# blinds_v60.net
KiCad netlist of a schematic drawn in EAGLE
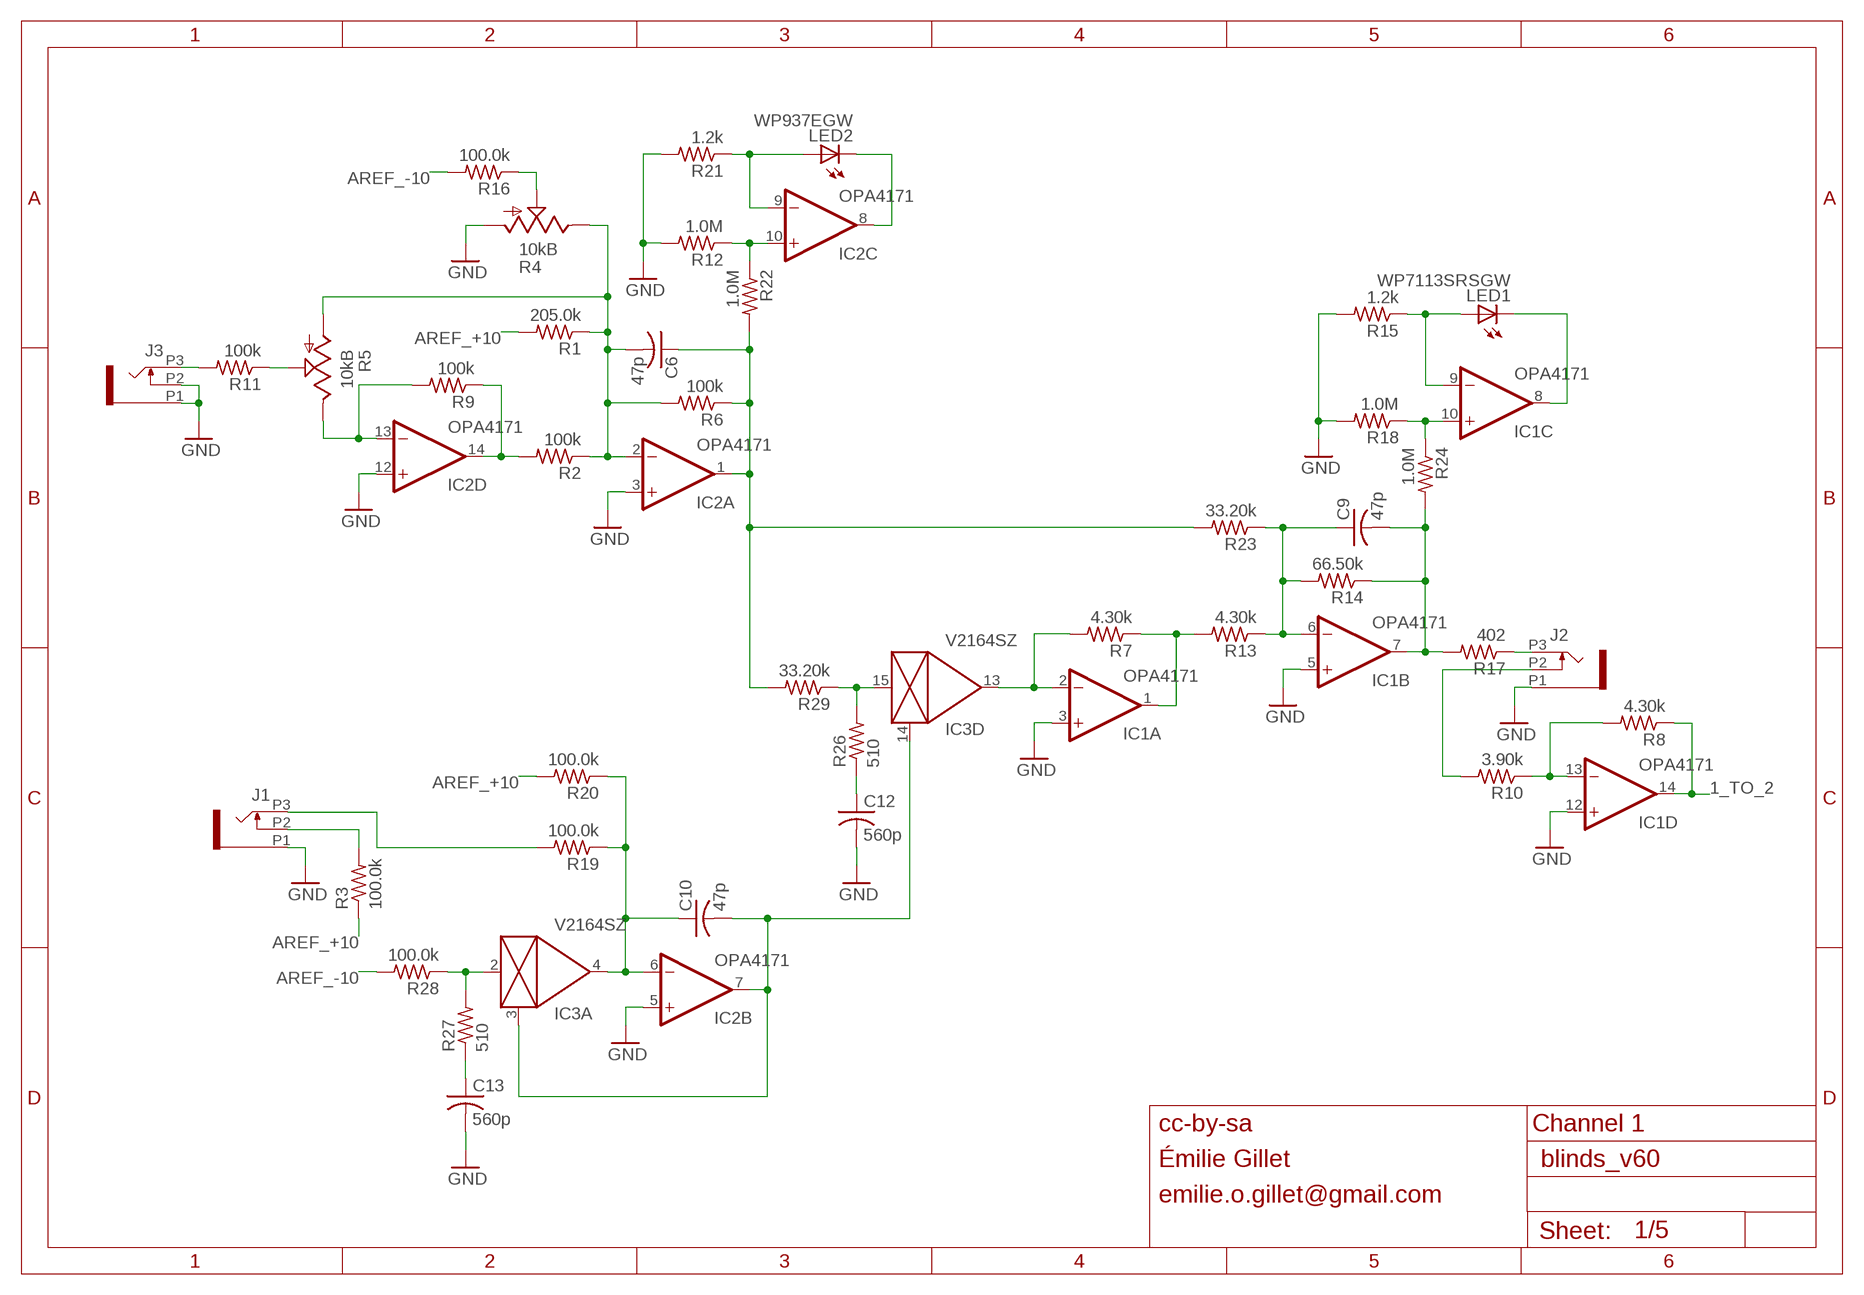
[diagram p0: schematic, sheet 1]
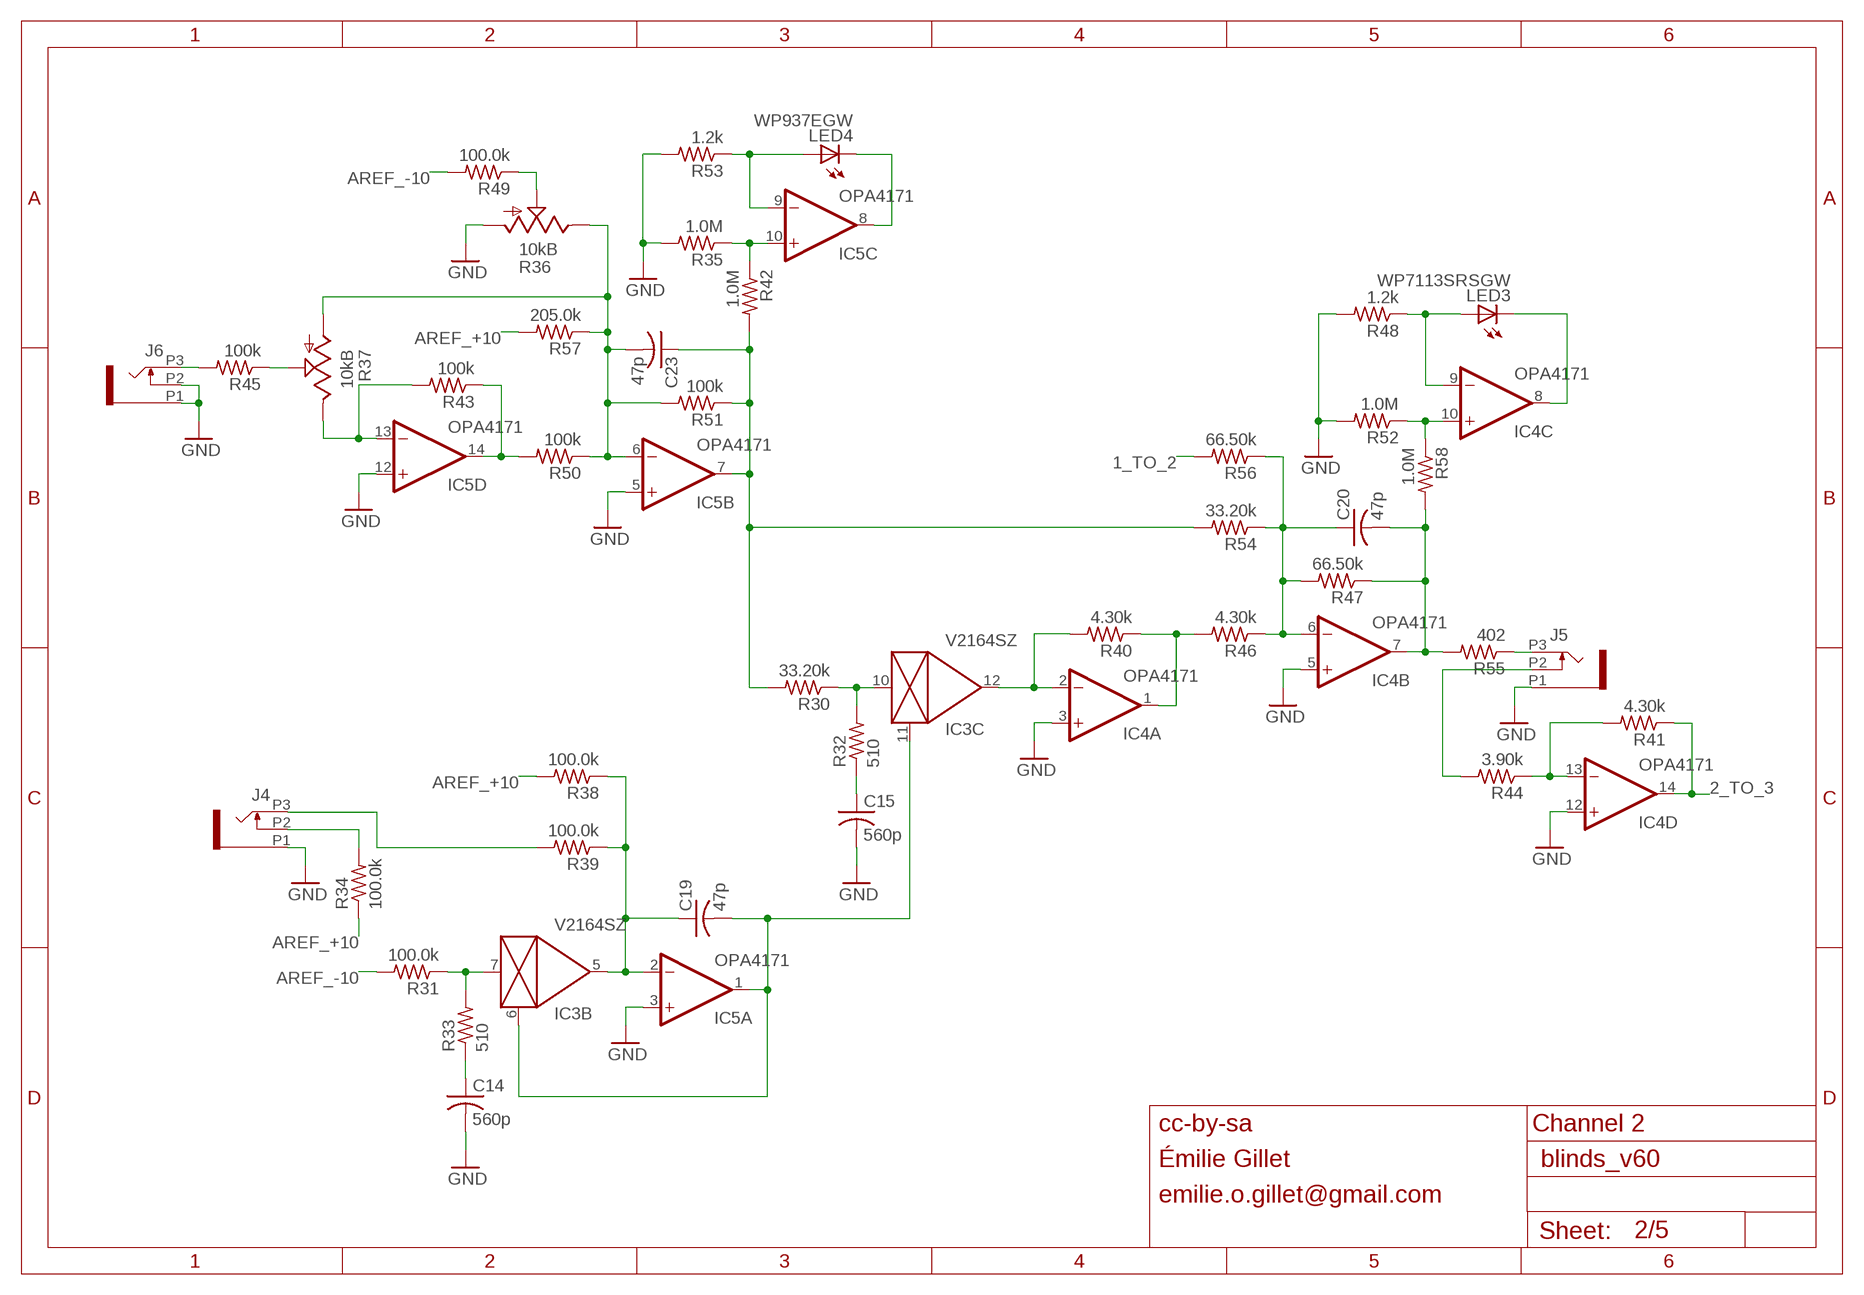
[diagram p1: schematic, sheet 2]
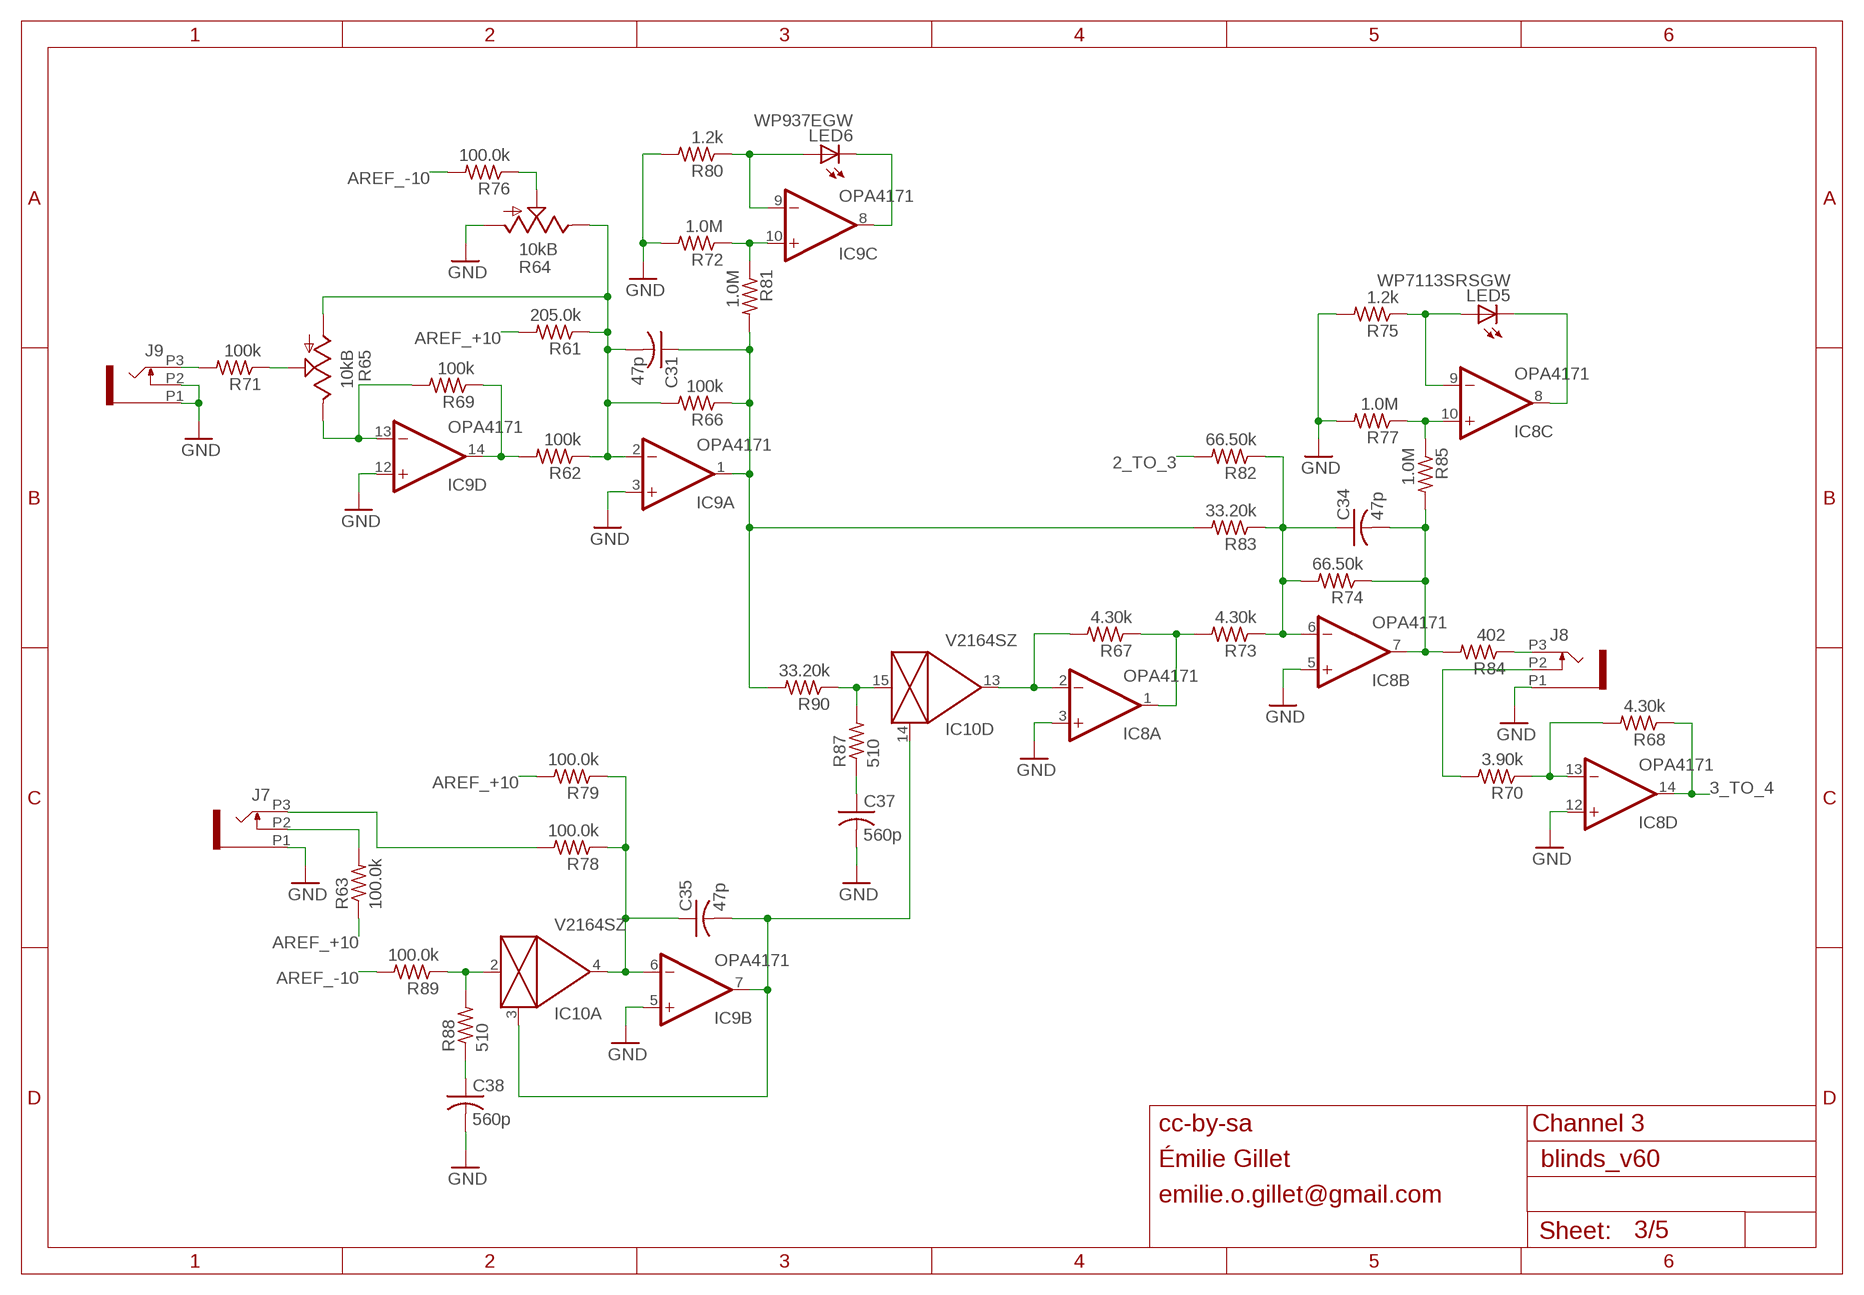
[diagram p2: schematic, sheet 3]
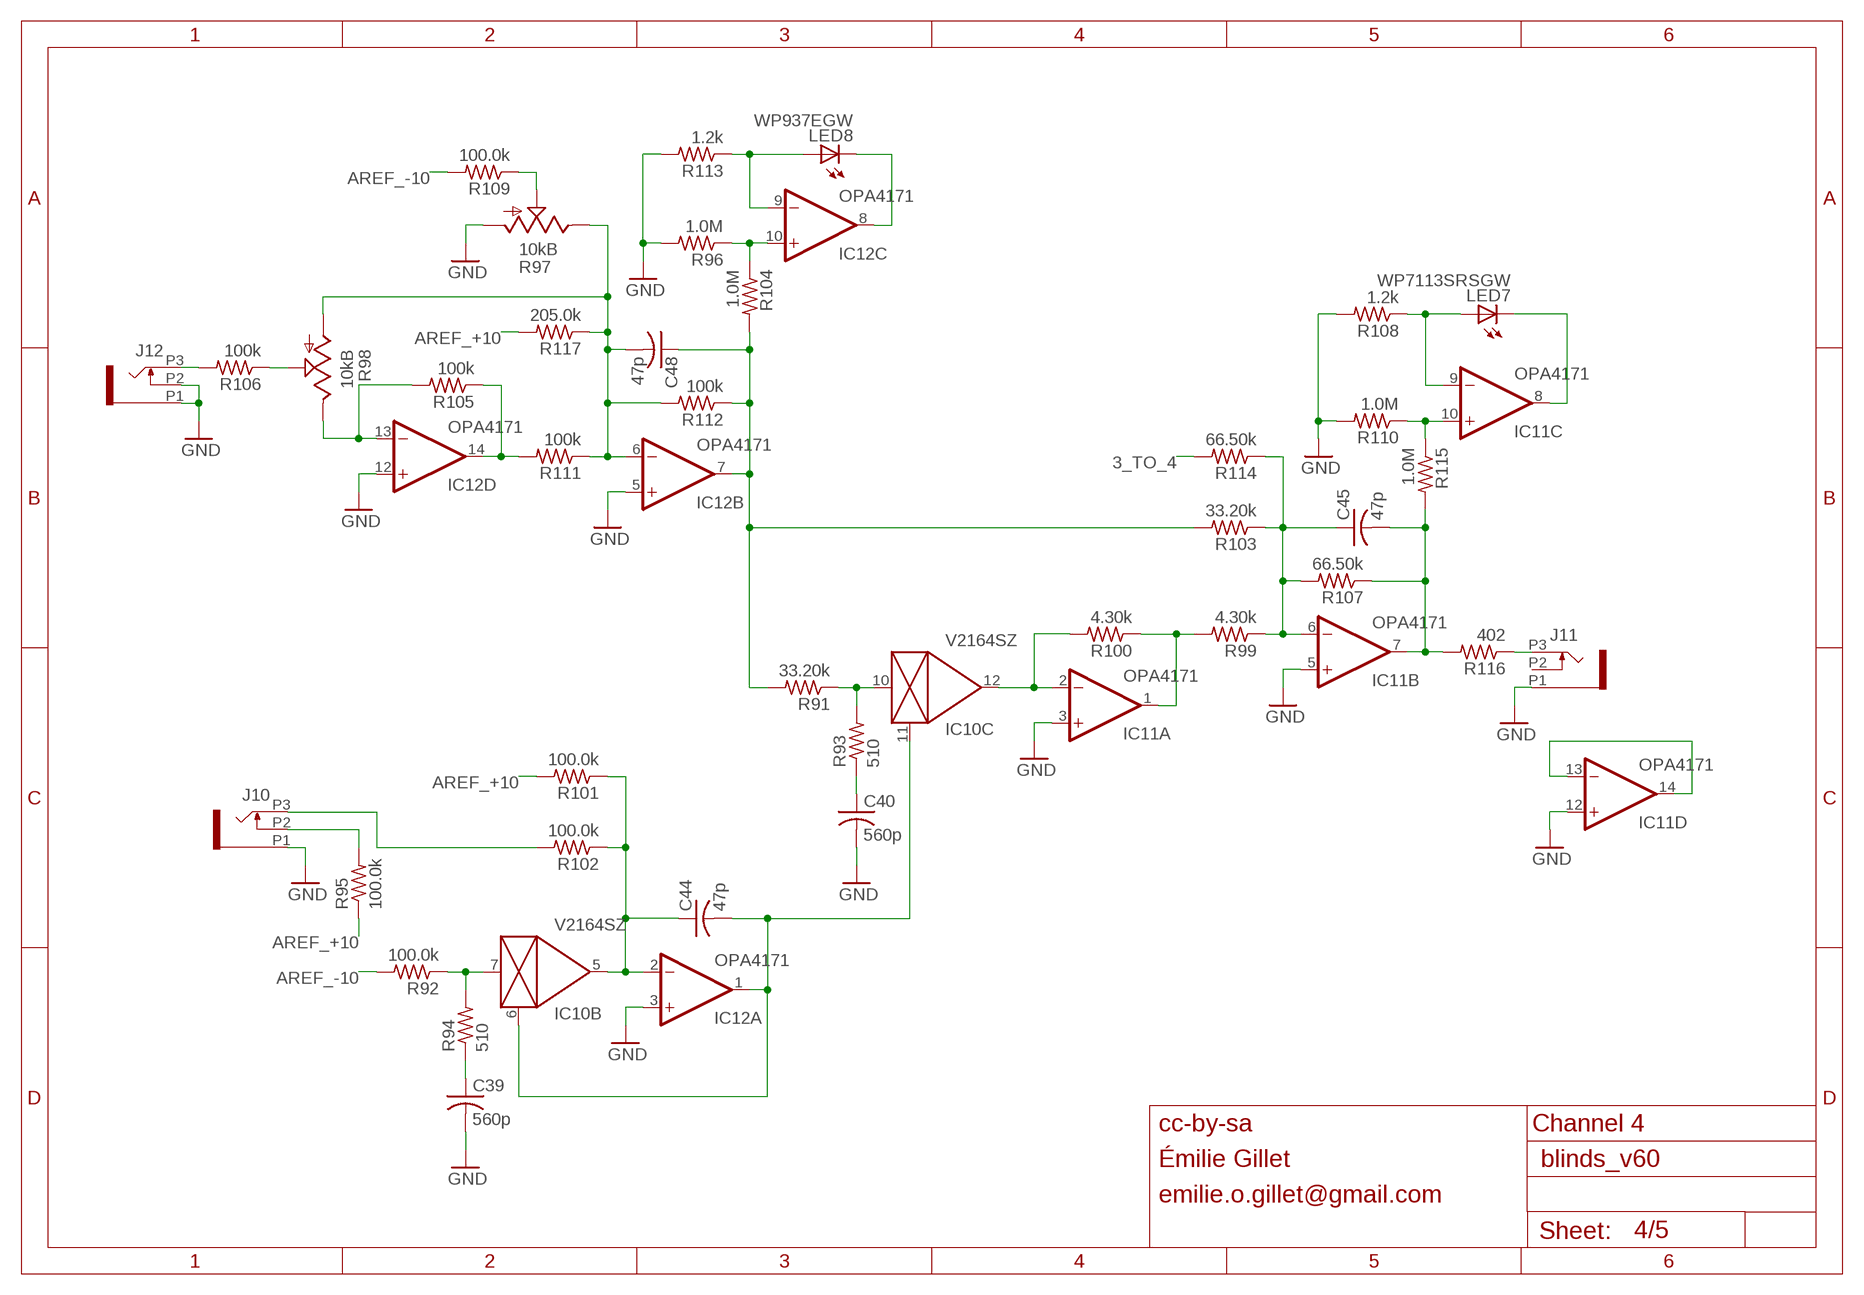
[diagram p3: schematic, sheet 4]
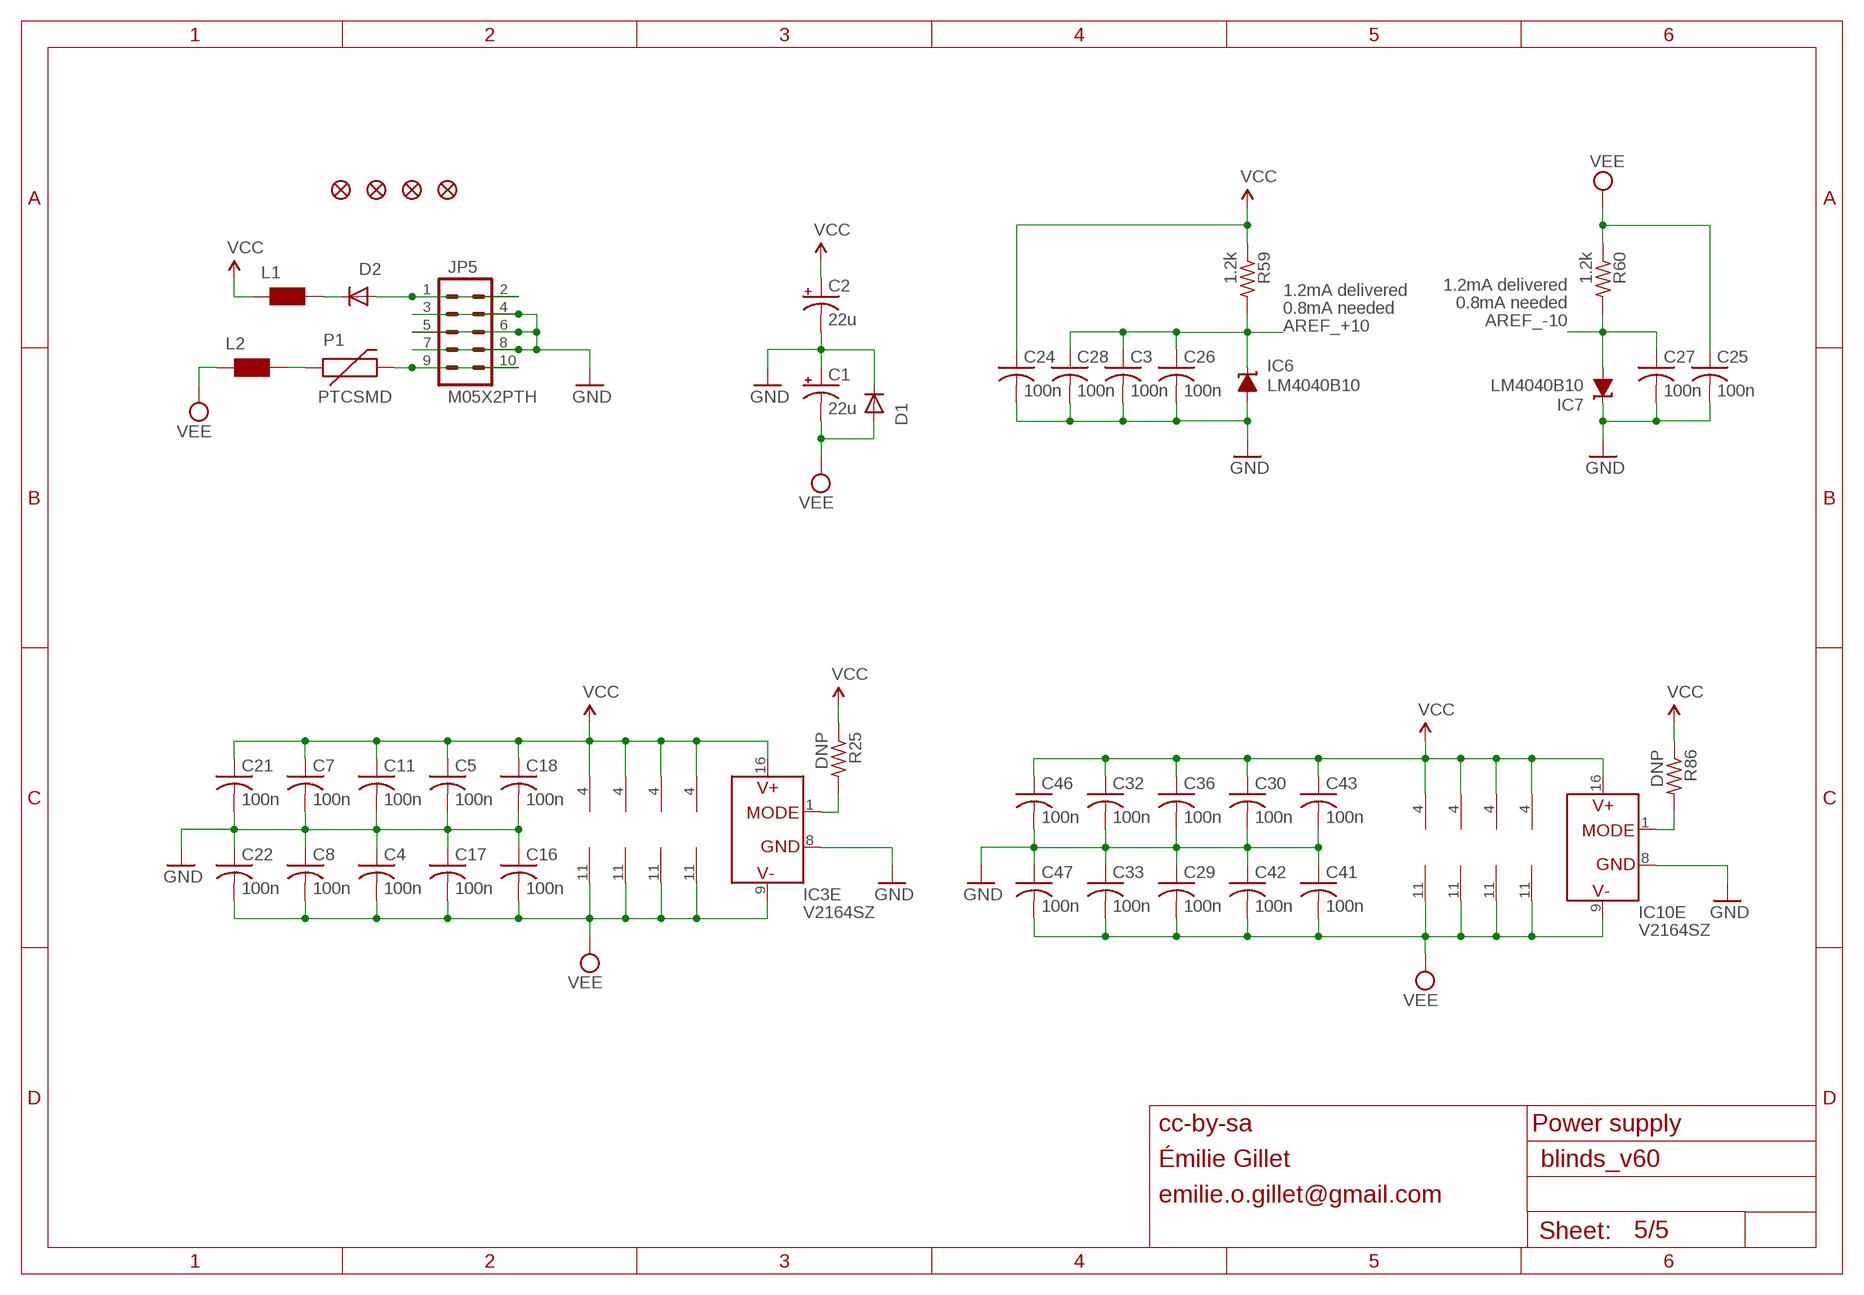
[diagram p4: schematic, sheet 5]

(export (version "E")
  (design (tool "Eeschema 10.0.6"))
  (components
    (comp (ref "C39")
      (value "560p")
      (footprint "eagle-import:C0603")
      (libsource (lib "eagle-import") (part "C-USC0603"))
    )
    (comp (ref "C40")
      (value "560p")
      (footprint "eagle-import:C0603")
      (libsource (lib "eagle-import") (part "C-USC0603"))
    )
    (comp (ref "C44")
      (value "47p")
      (footprint "eagle-import:C0603")
      (libsource (lib "eagle-import") (part "C-USC0603"))
    )
    (comp (ref "C45")
      (value "47p")
      (footprint "eagle-import:C0603")
      (libsource (lib "eagle-import") (part "C-USC0603"))
    )
    (comp (ref "C48")
      (value "47p")
      (footprint "eagle-import:C0603")
      (libsource (lib "eagle-import") (part "C-USC0603"))
    )
    (comp (ref "IC10")
      (value "V2164SZ")
      (footprint "eagle-import:SOIC16N")
      (libsource (lib "eagle-import") (part "SSM2164S"))
    )
    (comp (ref "IC11")
      (value "OPA4171")
      (footprint "eagle-import:TSSOP14")
      (libsource (lib "eagle-import") (part "TL074PW"))
    )
    (comp (ref "IC12")
      (value "OPA4171")
      (footprint "eagle-import:TSSOP14")
      (libsource (lib "eagle-import") (part "TL074PW"))
    )
    (comp (ref "J10")
      (value "PJ301_THONKICONN6")
      (footprint "eagle-import:WQP_PJ_301M6")
      (libsource (lib "eagle-import") (part "PJ301_THONKICONN6"))
    )
    (comp (ref "J11")
      (value "PJ301_THONKICONN6")
      (footprint "eagle-import:WQP_PJ_301M6")
      (libsource (lib "eagle-import") (part "PJ301_THONKICONN6"))
    )
    (comp (ref "J12")
      (value "PJ301_THONKICONN6")
      (footprint "eagle-import:WQP_PJ_301M6")
      (libsource (lib "eagle-import") (part "PJ301_THONKICONN6"))
    )
    (comp (ref "LED7")
      (value "WP7113SRSGW")
      (footprint "eagle-import:LED5MM")
      (libsource (lib "eagle-import") (part "LED5MM"))
    )
    (comp (ref "LED8")
      (value "WP937EGW")
      (footprint "eagle-import:LED3MM")
      (libsource (lib "eagle-import") (part "LED3MM"))
    )
    (comp (ref "R91")
      (value "33.20k")
      (footprint "eagle-import:R0603")
      (libsource (lib "eagle-import") (part "R-US_R0603"))
    )
    (comp (ref "R92")
      (value "100.0k")
      (footprint "eagle-import:R0603")
      (libsource (lib "eagle-import") (part "R-US_R0603"))
    )
    (comp (ref "R93")
      (value "510")
      (footprint "eagle-import:R0603")
      (libsource (lib "eagle-import") (part "R-US_R0603"))
    )
    (comp (ref "R94")
      (value "510")
      (footprint "eagle-import:R0603")
      (libsource (lib "eagle-import") (part "R-US_R0603"))
    )
    (comp (ref "R95")
      (value "100.0k")
      (footprint "eagle-import:R0603")
      (libsource (lib "eagle-import") (part "R-US_R0603"))
    )
    (comp (ref "R96")
      (value "1.0M")
      (footprint "eagle-import:R0603")
      (libsource (lib "eagle-import") (part "R-US_R0603"))
    )
    (comp (ref "R97")
      (value "10kB")
      (footprint "eagle-import:ALPS_POT_VERTICAL_PS")
      (libsource (lib "eagle-import") (part "POT_USVERTICAL_PS"))
    )
    (comp (ref "R98")
      (value "10kB")
      (footprint "eagle-import:ALPS_POT_VERTICAL")
      (libsource (lib "eagle-import") (part "POT_USVERTICAL"))
    )
    (comp (ref "R99")
      (value "4.30k")
      (footprint "eagle-import:R0603")
      (libsource (lib "eagle-import") (part "R-US_R0603"))
    )
    (comp (ref "R100")
      (value "4.30k")
      (footprint "eagle-import:R0603")
      (libsource (lib "eagle-import") (part "R-US_R0603"))
    )
    (comp (ref "R101")
      (value "100.0k")
      (footprint "eagle-import:R0603")
      (libsource (lib "eagle-import") (part "R-US_R0603"))
    )
    (comp (ref "R102")
      (value "100.0k")
      (footprint "eagle-import:R0603")
      (libsource (lib "eagle-import") (part "R-US_R0603"))
    )
    (comp (ref "R103")
      (value "33.20k")
      (footprint "eagle-import:R0603")
      (libsource (lib "eagle-import") (part "R-US_R0603"))
    )
    (comp (ref "R104")
      (value "1.0M")
      (footprint "eagle-import:R0603")
      (libsource (lib "eagle-import") (part "R-US_R0603"))
    )
    (comp (ref "R105")
      (value "100k")
      (footprint "eagle-import:R0603")
      (libsource (lib "eagle-import") (part "R-US_R0603"))
    )
    (comp (ref "R106")
      (value "100k")
      (footprint "eagle-import:R0603")
      (libsource (lib "eagle-import") (part "R-US_R0603"))
    )
    (comp (ref "R107")
      (value "66.50k")
      (footprint "eagle-import:R0603")
      (libsource (lib "eagle-import") (part "R-US_R0603"))
    )
    (comp (ref "R108")
      (value "1.2k")
      (footprint "eagle-import:R0603")
      (libsource (lib "eagle-import") (part "R-US_R0603"))
    )
    (comp (ref "R109")
      (value "100.0k")
      (footprint "eagle-import:R0603")
      (libsource (lib "eagle-import") (part "R-US_R0603"))
    )
    (comp (ref "R110")
      (value "1.0M")
      (footprint "eagle-import:R0603")
      (libsource (lib "eagle-import") (part "R-US_R0603"))
    )
    (comp (ref "R111")
      (value "100k")
      (footprint "eagle-import:R0603")
      (libsource (lib "eagle-import") (part "R-US_R0603"))
    )
    (comp (ref "R112")
      (value "100k")
      (footprint "eagle-import:R0603")
      (libsource (lib "eagle-import") (part "R-US_R0603"))
    )
    (comp (ref "R113")
      (value "1.2k")
      (footprint "eagle-import:R0603")
      (libsource (lib "eagle-import") (part "R-US_R0603"))
    )
    (comp (ref "R114")
      (value "66.50k")
      (footprint "eagle-import:R0603")
      (libsource (lib "eagle-import") (part "R-US_R0603"))
    )
    (comp (ref "R115")
      (value "1.0M")
      (footprint "eagle-import:R0603")
      (libsource (lib "eagle-import") (part "R-US_R0603"))
    )
    (comp (ref "R116")
      (value "402")
      (footprint "eagle-import:R0603")
      (libsource (lib "eagle-import") (part "R-US_R0603"))
    )
    (comp (ref "R117")
      (value "205.0k")
      (footprint "eagle-import:R0603")
      (libsource (lib "eagle-import") (part "R-US_R0603"))
    )
    (comp (ref "C14")
      (value "560p")
      (footprint "eagle-import:C0603")
      (libsource (lib "eagle-import") (part "C-USC0603"))
    )
    (comp (ref "C15")
      (value "560p")
      (footprint "eagle-import:C0603")
      (libsource (lib "eagle-import") (part "C-USC0603"))
    )
    (comp (ref "C19")
      (value "47p")
      (footprint "eagle-import:C0603")
      (libsource (lib "eagle-import") (part "C-USC0603"))
    )
    (comp (ref "C20")
      (value "47p")
      (footprint "eagle-import:C0603")
      (libsource (lib "eagle-import") (part "C-USC0603"))
    )
    (comp (ref "C23")
      (value "47p")
      (footprint "eagle-import:C0603")
      (libsource (lib "eagle-import") (part "C-USC0603"))
    )
    (comp (ref "IC3")
      (value "V2164SZ")
      (footprint "eagle-import:SOIC16N")
      (libsource (lib "eagle-import") (part "SSM2164S"))
    )
    (comp (ref "IC4")
      (value "OPA4171")
      (footprint "eagle-import:TSSOP14")
      (libsource (lib "eagle-import") (part "TL074PW"))
    )
    (comp (ref "IC5")
      (value "OPA4171")
      (footprint "eagle-import:TSSOP14")
      (libsource (lib "eagle-import") (part "TL074PW"))
    )
    (comp (ref "J4")
      (value "PJ301_THONKICONN6")
      (footprint "eagle-import:WQP_PJ_301M6")
      (libsource (lib "eagle-import") (part "PJ301_THONKICONN6"))
    )
    (comp (ref "J5")
      (value "PJ301_THONKICONN6")
      (footprint "eagle-import:WQP_PJ_301M6")
      (libsource (lib "eagle-import") (part "PJ301_THONKICONN6"))
    )
    (comp (ref "J6")
      (value "PJ301_THONKICONN6")
      (footprint "eagle-import:WQP_PJ_301M6")
      (libsource (lib "eagle-import") (part "PJ301_THONKICONN6"))
    )
    (comp (ref "LED3")
      (value "WP7113SRSGW")
      (footprint "eagle-import:LED5MM")
      (libsource (lib "eagle-import") (part "LED5MM"))
    )
    (comp (ref "LED4")
      (value "WP937EGW")
      (footprint "eagle-import:LED3MM")
      (libsource (lib "eagle-import") (part "LED3MM"))
    )
    (comp (ref "R30")
      (value "33.20k")
      (footprint "eagle-import:R0603")
      (libsource (lib "eagle-import") (part "R-US_R0603"))
    )
    (comp (ref "R31")
      (value "100.0k")
      (footprint "eagle-import:R0603")
      (libsource (lib "eagle-import") (part "R-US_R0603"))
    )
    (comp (ref "R32")
      (value "510")
      (footprint "eagle-import:R0603")
      (libsource (lib "eagle-import") (part "R-US_R0603"))
    )
    (comp (ref "R33")
      (value "510")
      (footprint "eagle-import:R0603")
      (libsource (lib "eagle-import") (part "R-US_R0603"))
    )
    (comp (ref "R34")
      (value "100.0k")
      (footprint "eagle-import:R0603")
      (libsource (lib "eagle-import") (part "R-US_R0603"))
    )
    (comp (ref "R35")
      (value "1.0M")
      (footprint "eagle-import:R0603")
      (libsource (lib "eagle-import") (part "R-US_R0603"))
    )
    (comp (ref "R36")
      (value "10kB")
      (footprint "eagle-import:ALPS_POT_VERTICAL_PS")
      (libsource (lib "eagle-import") (part "POT_USVERTICAL_PS"))
    )
    (comp (ref "R37")
      (value "10kB")
      (footprint "eagle-import:ALPS_POT_VERTICAL")
      (libsource (lib "eagle-import") (part "POT_USVERTICAL"))
    )
    (comp (ref "R38")
      (value "100.0k")
      (footprint "eagle-import:R0603")
      (libsource (lib "eagle-import") (part "R-US_R0603"))
    )
    (comp (ref "R39")
      (value "100.0k")
      (footprint "eagle-import:R0603")
      (libsource (lib "eagle-import") (part "R-US_R0603"))
    )
    (comp (ref "R40")
      (value "4.30k")
      (footprint "eagle-import:R0603")
      (libsource (lib "eagle-import") (part "R-US_R0603"))
    )
    (comp (ref "R41")
      (value "4.30k")
      (footprint "eagle-import:R0603")
      (libsource (lib "eagle-import") (part "R-US_R0603"))
    )
    (comp (ref "R42")
      (value "1.0M")
      (footprint "eagle-import:R0603")
      (libsource (lib "eagle-import") (part "R-US_R0603"))
    )
    (comp (ref "R43")
      (value "100k")
      (footprint "eagle-import:R0603")
      (libsource (lib "eagle-import") (part "R-US_R0603"))
    )
    (comp (ref "R44")
      (value "3.90k")
      (footprint "eagle-import:R0603")
      (libsource (lib "eagle-import") (part "R-US_R0603"))
    )
    (comp (ref "R45")
      (value "100k")
      (footprint "eagle-import:R0603")
      (libsource (lib "eagle-import") (part "R-US_R0603"))
    )
    (comp (ref "R46")
      (value "4.30k")
      (footprint "eagle-import:R0603")
      (libsource (lib "eagle-import") (part "R-US_R0603"))
    )
    (comp (ref "R47")
      (value "66.50k")
      (footprint "eagle-import:R0603")
      (libsource (lib "eagle-import") (part "R-US_R0603"))
    )
    (comp (ref "R48")
      (value "1.2k")
      (footprint "eagle-import:R0603")
      (libsource (lib "eagle-import") (part "R-US_R0603"))
    )
    (comp (ref "R49")
      (value "100.0k")
      (footprint "eagle-import:R0603")
      (libsource (lib "eagle-import") (part "R-US_R0603"))
    )
    (comp (ref "R50")
      (value "100k")
      (footprint "eagle-import:R0603")
      (libsource (lib "eagle-import") (part "R-US_R0603"))
    )
    (comp (ref "R51")
      (value "100k")
      (footprint "eagle-import:R0603")
      (libsource (lib "eagle-import") (part "R-US_R0603"))
    )
    (comp (ref "R52")
      (value "1.0M")
      (footprint "eagle-import:R0603")
      (libsource (lib "eagle-import") (part "R-US_R0603"))
    )
    (comp (ref "R53")
      (value "1.2k")
      (footprint "eagle-import:R0603")
      (libsource (lib "eagle-import") (part "R-US_R0603"))
    )
    (comp (ref "R54")
      (value "33.20k")
      (footprint "eagle-import:R0603")
      (libsource (lib "eagle-import") (part "R-US_R0603"))
    )
    (comp (ref "R55")
      (value "402")
      (footprint "eagle-import:R0603")
      (libsource (lib "eagle-import") (part "R-US_R0603"))
    )
    (comp (ref "R56")
      (value "66.50k")
      (footprint "eagle-import:R0603")
      (libsource (lib "eagle-import") (part "R-US_R0603"))
    )
    (comp (ref "R57")
      (value "205.0k")
      (footprint "eagle-import:R0603")
      (libsource (lib "eagle-import") (part "R-US_R0603"))
    )
    (comp (ref "R58")
      (value "1.0M")
      (footprint "eagle-import:R0603")
      (libsource (lib "eagle-import") (part "R-US_R0603"))
    )
    (comp (ref "C6")
      (value "47p")
      (footprint "eagle-import:C0603")
      (libsource (lib "eagle-import") (part "C-USC0603"))
    )
    (comp (ref "C9")
      (value "47p")
      (footprint "eagle-import:C0603")
      (libsource (lib "eagle-import") (part "C-USC0603"))
    )
    (comp (ref "C10")
      (value "47p")
      (footprint "eagle-import:C0603")
      (libsource (lib "eagle-import") (part "C-USC0603"))
    )
    (comp (ref "C12")
      (value "560p")
      (footprint "eagle-import:C0603")
      (libsource (lib "eagle-import") (part "C-USC0603"))
    )
    (comp (ref "C13")
      (value "560p")
      (footprint "eagle-import:C0603")
      (libsource (lib "eagle-import") (part "C-USC0603"))
    )
    (comp (ref "IC1")
      (value "OPA4171")
      (footprint "eagle-import:TSSOP14")
      (libsource (lib "eagle-import") (part "TL074PW"))
    )
    (comp (ref "IC2")
      (value "OPA4171")
      (footprint "eagle-import:TSSOP14")
      (libsource (lib "eagle-import") (part "TL074PW"))
    )
    (comp (ref "J1")
      (value "PJ301_THONKICONN6")
      (footprint "eagle-import:WQP_PJ_301M6")
      (libsource (lib "eagle-import") (part "PJ301_THONKICONN6"))
    )
    (comp (ref "J2")
      (value "PJ301_THONKICONN6")
      (footprint "eagle-import:WQP_PJ_301M6")
      (libsource (lib "eagle-import") (part "PJ301_THONKICONN6"))
    )
    (comp (ref "J3")
      (value "PJ301_THONKICONN6")
      (footprint "eagle-import:WQP_PJ_301M6")
      (libsource (lib "eagle-import") (part "PJ301_THONKICONN6"))
    )
    (comp (ref "LED1")
      (value "WP7113SRSGW")
      (footprint "eagle-import:LED5MM")
      (libsource (lib "eagle-import") (part "LED5MM"))
    )
    (comp (ref "LED2")
      (value "WP937EGW")
      (footprint "eagle-import:LED3MM")
      (libsource (lib "eagle-import") (part "LED3MM"))
    )
    (comp (ref "R1")
      (value "205.0k")
      (footprint "eagle-import:R0603")
      (libsource (lib "eagle-import") (part "R-US_R0603"))
    )
    (comp (ref "R2")
      (value "100k")
      (footprint "eagle-import:R0603")
      (libsource (lib "eagle-import") (part "R-US_R0603"))
    )
    (comp (ref "R3")
      (value "100.0k")
      (footprint "eagle-import:R0603")
      (libsource (lib "eagle-import") (part "R-US_R0603"))
    )
    (comp (ref "R4")
      (value "10kB")
      (footprint "eagle-import:ALPS_POT_VERTICAL_PS")
      (libsource (lib "eagle-import") (part "POT_USVERTICAL_PS"))
    )
    (comp (ref "R5")
      (value "10kB")
      (footprint "eagle-import:ALPS_POT_VERTICAL")
      (libsource (lib "eagle-import") (part "POT_USVERTICAL"))
    )
    (comp (ref "R6")
      (value "100k")
      (footprint "eagle-import:R0603")
      (libsource (lib "eagle-import") (part "R-US_R0603"))
    )
    (comp (ref "R7")
      (value "4.30k")
      (footprint "eagle-import:R0603")
      (libsource (lib "eagle-import") (part "R-US_R0603"))
    )
    (comp (ref "R8")
      (value "4.30k")
      (footprint "eagle-import:R0603")
      (libsource (lib "eagle-import") (part "R-US_R0603"))
    )
    (comp (ref "R9")
      (value "100k")
      (footprint "eagle-import:R0603")
      (libsource (lib "eagle-import") (part "R-US_R0603"))
    )
    (comp (ref "R10")
      (value "3.90k")
      (footprint "eagle-import:R0603")
      (libsource (lib "eagle-import") (part "R-US_R0603"))
    )
    (comp (ref "R11")
      (value "100k")
      (footprint "eagle-import:R0603")
      (libsource (lib "eagle-import") (part "R-US_R0603"))
    )
    (comp (ref "R12")
      (value "1.0M")
      (footprint "eagle-import:R0603")
      (libsource (lib "eagle-import") (part "R-US_R0603"))
    )
    (comp (ref "R13")
      (value "4.30k")
      (footprint "eagle-import:R0603")
      (libsource (lib "eagle-import") (part "R-US_R0603"))
    )
    (comp (ref "R14")
      (value "66.50k")
      (footprint "eagle-import:R0603")
      (libsource (lib "eagle-import") (part "R-US_R0603"))
    )
    (comp (ref "R15")
      (value "1.2k")
      (footprint "eagle-import:R0603")
      (libsource (lib "eagle-import") (part "R-US_R0603"))
    )
    (comp (ref "R16")
      (value "100.0k")
      (footprint "eagle-import:R0603")
      (libsource (lib "eagle-import") (part "R-US_R0603"))
    )
    (comp (ref "R17")
      (value "402")
      (footprint "eagle-import:R0603")
      (libsource (lib "eagle-import") (part "R-US_R0603"))
    )
    (comp (ref "R18")
      (value "1.0M")
      (footprint "eagle-import:R0603")
      (libsource (lib "eagle-import") (part "R-US_R0603"))
    )
    (comp (ref "R19")
      (value "100.0k")
      (footprint "eagle-import:R0603")
      (libsource (lib "eagle-import") (part "R-US_R0603"))
    )
    (comp (ref "R20")
      (value "100.0k")
      (footprint "eagle-import:R0603")
      (libsource (lib "eagle-import") (part "R-US_R0603"))
    )
    (comp (ref "R21")
      (value "1.2k")
      (footprint "eagle-import:R0603")
      (libsource (lib "eagle-import") (part "R-US_R0603"))
    )
    (comp (ref "R22")
      (value "1.0M")
      (footprint "eagle-import:R0603")
      (libsource (lib "eagle-import") (part "R-US_R0603"))
    )
    (comp (ref "R23")
      (value "33.20k")
      (footprint "eagle-import:R0603")
      (libsource (lib "eagle-import") (part "R-US_R0603"))
    )
    (comp (ref "R24")
      (value "1.0M")
      (footprint "eagle-import:R0603")
      (libsource (lib "eagle-import") (part "R-US_R0603"))
    )
    (comp (ref "R26")
      (value "510")
      (footprint "eagle-import:R0603")
      (libsource (lib "eagle-import") (part "R-US_R0603"))
    )
    (comp (ref "R27")
      (value "510")
      (footprint "eagle-import:R0603")
      (libsource (lib "eagle-import") (part "R-US_R0603"))
    )
    (comp (ref "R28")
      (value "100.0k")
      (footprint "eagle-import:R0603")
      (libsource (lib "eagle-import") (part "R-US_R0603"))
    )
    (comp (ref "R29")
      (value "33.20k")
      (footprint "eagle-import:R0603")
      (libsource (lib "eagle-import") (part "R-US_R0603"))
    )
    (comp (ref "C1")
      (value "22u")
      (footprint "eagle-import:PANASONIC_C")
      (libsource (lib "eagle-import") (part "CPOL-USC"))
    )
    (comp (ref "C2")
      (value "22u")
      (footprint "eagle-import:PANASONIC_C")
      (libsource (lib "eagle-import") (part "CPOL-USC"))
    )
    (comp (ref "C3")
      (value "100n")
      (footprint "eagle-import:C0603")
      (libsource (lib "eagle-import") (part "C-USC0603"))
    )
    (comp (ref "C4")
      (value "100n")
      (footprint "eagle-import:C0603")
      (libsource (lib "eagle-import") (part "C-USC0603"))
    )
    (comp (ref "C5")
      (value "100n")
      (footprint "eagle-import:C0603")
      (libsource (lib "eagle-import") (part "C-USC0603"))
    )
    (comp (ref "C7")
      (value "100n")
      (footprint "eagle-import:C0603")
      (libsource (lib "eagle-import") (part "C-USC0603"))
    )
    (comp (ref "C8")
      (value "100n")
      (footprint "eagle-import:C0603")
      (libsource (lib "eagle-import") (part "C-USC0603"))
    )
    (comp (ref "C11")
      (value "100n")
      (footprint "eagle-import:C0603")
      (libsource (lib "eagle-import") (part "C-USC0603"))
    )
    (comp (ref "C16")
      (value "100n")
      (footprint "eagle-import:C0603")
      (libsource (lib "eagle-import") (part "C-USC0603"))
    )
    (comp (ref "C17")
      (value "100n")
      (footprint "eagle-import:C0603")
      (libsource (lib "eagle-import") (part "C-USC0603"))
    )
    (comp (ref "C18")
      (value "100n")
      (footprint "eagle-import:C0603")
      (libsource (lib "eagle-import") (part "C-USC0603"))
    )
    (comp (ref "C21")
      (value "100n")
      (footprint "eagle-import:C0603")
      (libsource (lib "eagle-import") (part "C-USC0603"))
    )
    (comp (ref "C22")
      (value "100n")
      (footprint "eagle-import:C0603")
      (libsource (lib "eagle-import") (part "C-USC0603"))
    )
    (comp (ref "C24")
      (value "100n")
      (footprint "eagle-import:C0603")
      (libsource (lib "eagle-import") (part "C-USC0603"))
    )
    (comp (ref "C25")
      (value "100n")
      (footprint "eagle-import:C0603")
      (libsource (lib "eagle-import") (part "C-USC0603"))
    )
    (comp (ref "C26")
      (value "100n")
      (footprint "eagle-import:C0603")
      (libsource (lib "eagle-import") (part "C-USC0603"))
    )
    (comp (ref "C27")
      (value "100n")
      (footprint "eagle-import:C0603")
      (libsource (lib "eagle-import") (part "C-USC0603"))
    )
    (comp (ref "C28")
      (value "100n")
      (footprint "eagle-import:C0603")
      (libsource (lib "eagle-import") (part "C-USC0603"))
    )
    (comp (ref "C29")
      (value "100n")
      (footprint "eagle-import:C0603")
      (libsource (lib "eagle-import") (part "C-USC0603"))
    )
    (comp (ref "C30")
      (value "100n")
      (footprint "eagle-import:C0603")
      (libsource (lib "eagle-import") (part "C-USC0603"))
    )
    (comp (ref "C32")
      (value "100n")
      (footprint "eagle-import:C0603")
      (libsource (lib "eagle-import") (part "C-USC0603"))
    )
    (comp (ref "C33")
      (value "100n")
      (footprint "eagle-import:C0603")
      (libsource (lib "eagle-import") (part "C-USC0603"))
    )
    (comp (ref "C36")
      (value "100n")
      (footprint "eagle-import:C0603")
      (libsource (lib "eagle-import") (part "C-USC0603"))
    )
    (comp (ref "C41")
      (value "100n")
      (footprint "eagle-import:C0603")
      (libsource (lib "eagle-import") (part "C-USC0603"))
    )
    (comp (ref "C42")
      (value "100n")
      (footprint "eagle-import:C0603")
      (libsource (lib "eagle-import") (part "C-USC0603"))
    )
    (comp (ref "C43")
      (value "100n")
      (footprint "eagle-import:C0603")
      (libsource (lib "eagle-import") (part "C-USC0603"))
    )
    (comp (ref "C46")
      (value "100n")
      (footprint "eagle-import:C0603")
      (libsource (lib "eagle-import") (part "C-USC0603"))
    )
    (comp (ref "C47")
      (value "100n")
      (footprint "eagle-import:C0603")
      (libsource (lib "eagle-import") (part "C-USC0603"))
    )
    (comp (ref "D1")
      (value "1N5819HW")
      (footprint "eagle-import:SOD123")
      (libsource (lib "eagle-import") (part "DIODE-SOD123"))
    )
    (comp (ref "D2")
      (value "1N5819HW")
      (footprint "eagle-import:SOD123")
      (libsource (lib "eagle-import") (part "DIODE-SOD123"))
    )
    (comp (ref "IC6")
      (value "LM4040B10")
      (footprint "eagle-import:DBZ_R-PDSO-G3")
      (libsource (lib "eagle-import") (part "LM4041DBZB12"))
    )
    (comp (ref "IC7")
      (value "LM4040B10")
      (footprint "eagle-import:DBZ_R-PDSO-G3")
      (libsource (lib "eagle-import") (part "LM4041DBZB12"))
    )
    (comp (ref "IC8")
      (value "OPA4171")
      (footprint "eagle-import:TSSOP14")
      (libsource (lib "eagle-import") (part "TL074PW"))
    )
    (comp (ref "IC9")
      (value "OPA4171")
      (footprint "eagle-import:TSSOP14")
      (libsource (lib "eagle-import") (part "TL074PW"))
    )
    (comp (ref "JP1")
      (value "FIDUCIAL1X2")
      (footprint "eagle-import:FIDUCIAL-1X2")
      (libsource (lib "eagle-import") (part "FIDUCIAL1X2"))
    )
    (comp (ref "JP2")
      (value "FIDUCIAL1X2")
      (footprint "eagle-import:FIDUCIAL-1X2")
      (libsource (lib "eagle-import") (part "FIDUCIAL1X2"))
    )
    (comp (ref "JP3")
      (value "FIDUCIAL1X2")
      (footprint "eagle-import:FIDUCIAL-1X2")
      (libsource (lib "eagle-import") (part "FIDUCIAL1X2"))
    )
    (comp (ref "JP4")
      (value "FIDUCIAL1X2")
      (footprint "eagle-import:FIDUCIAL-1X2")
      (libsource (lib "eagle-import") (part "FIDUCIAL1X2"))
    )
    (comp (ref "JP5")
      (value "M05X2PTH")
      (footprint "eagle-import:AVR_ICSP")
      (libsource (lib "eagle-import") (part "M05X2PTH"))
    )
    (comp (ref "L1")
      (value "WE-CBF_0603")
      (footprint "eagle-import:0603")
      (libsource (lib "eagle-import") (part "WE-CBF_0603"))
    )
    (comp (ref "L2")
      (value "WE-CBF_0603")
      (footprint "eagle-import:0603")
      (libsource (lib "eagle-import") (part "WE-CBF_0603"))
    )
    (comp (ref "P1")
      (value "PTCSMD")
      (footprint "eagle-import:PTC-1206")
      (libsource (lib "eagle-import") (part "PTCSMD"))
    )
    (comp (ref "R25")
      (value "DNP")
      (footprint "eagle-import:R0603")
      (libsource (lib "eagle-import") (part "R-US_R0603"))
    )
    (comp (ref "R59")
      (value "1.2k")
      (footprint "eagle-import:R0603")
      (libsource (lib "eagle-import") (part "R-US_R0603"))
    )
    (comp (ref "R60")
      (value "1.2k")
      (footprint "eagle-import:R0603")
      (libsource (lib "eagle-import") (part "R-US_R0603"))
    )
    (comp (ref "R86")
      (value "DNP")
      (footprint "eagle-import:R0603")
      (libsource (lib "eagle-import") (part "R-US_R0603"))
    )
    (comp (ref "C31")
      (value "47p")
      (footprint "eagle-import:C0603")
      (libsource (lib "eagle-import") (part "C-USC0603"))
    )
    (comp (ref "C34")
      (value "47p")
      (footprint "eagle-import:C0603")
      (libsource (lib "eagle-import") (part "C-USC0603"))
    )
    (comp (ref "C35")
      (value "47p")
      (footprint "eagle-import:C0603")
      (libsource (lib "eagle-import") (part "C-USC0603"))
    )
    (comp (ref "C37")
      (value "560p")
      (footprint "eagle-import:C0603")
      (libsource (lib "eagle-import") (part "C-USC0603"))
    )
    (comp (ref "C38")
      (value "560p")
      (footprint "eagle-import:C0603")
      (libsource (lib "eagle-import") (part "C-USC0603"))
    )
    (comp (ref "J7")
      (value "PJ301_THONKICONN6")
      (footprint "eagle-import:WQP_PJ_301M6")
      (libsource (lib "eagle-import") (part "PJ301_THONKICONN6"))
    )
    (comp (ref "J8")
      (value "PJ301_THONKICONN6")
      (footprint "eagle-import:WQP_PJ_301M6")
      (libsource (lib "eagle-import") (part "PJ301_THONKICONN6"))
    )
    (comp (ref "J9")
      (value "PJ301_THONKICONN6")
      (footprint "eagle-import:WQP_PJ_301M6")
      (libsource (lib "eagle-import") (part "PJ301_THONKICONN6"))
    )
    (comp (ref "LED5")
      (value "WP7113SRSGW")
      (footprint "eagle-import:LED5MM")
      (libsource (lib "eagle-import") (part "LED5MM"))
    )
    (comp (ref "LED6")
      (value "WP937EGW")
      (footprint "eagle-import:LED3MM")
      (libsource (lib "eagle-import") (part "LED3MM"))
    )
    (comp (ref "R61")
      (value "205.0k")
      (footprint "eagle-import:R0603")
      (libsource (lib "eagle-import") (part "R-US_R0603"))
    )
    (comp (ref "R62")
      (value "100k")
      (footprint "eagle-import:R0603")
      (libsource (lib "eagle-import") (part "R-US_R0603"))
    )
    (comp (ref "R63")
      (value "100.0k")
      (footprint "eagle-import:R0603")
      (libsource (lib "eagle-import") (part "R-US_R0603"))
    )
    (comp (ref "R64")
      (value "10kB")
      (footprint "eagle-import:ALPS_POT_VERTICAL_PS")
      (libsource (lib "eagle-import") (part "POT_USVERTICAL_PS"))
    )
    (comp (ref "R65")
      (value "10kB")
      (footprint "eagle-import:ALPS_POT_VERTICAL")
      (libsource (lib "eagle-import") (part "POT_USVERTICAL"))
    )
    (comp (ref "R66")
      (value "100k")
      (footprint "eagle-import:R0603")
      (libsource (lib "eagle-import") (part "R-US_R0603"))
    )
    (comp (ref "R67")
      (value "4.30k")
      (footprint "eagle-import:R0603")
      (libsource (lib "eagle-import") (part "R-US_R0603"))
    )
    (comp (ref "R68")
      (value "4.30k")
      (footprint "eagle-import:R0603")
      (libsource (lib "eagle-import") (part "R-US_R0603"))
    )
    (comp (ref "R69")
      (value "100k")
      (footprint "eagle-import:R0603")
      (libsource (lib "eagle-import") (part "R-US_R0603"))
    )
    (comp (ref "R70")
      (value "3.90k")
      (footprint "eagle-import:R0603")
      (libsource (lib "eagle-import") (part "R-US_R0603"))
    )
    (comp (ref "R71")
      (value "100k")
      (footprint "eagle-import:R0603")
      (libsource (lib "eagle-import") (part "R-US_R0603"))
    )
    (comp (ref "R72")
      (value "1.0M")
      (footprint "eagle-import:R0603")
      (libsource (lib "eagle-import") (part "R-US_R0603"))
    )
    (comp (ref "R73")
      (value "4.30k")
      (footprint "eagle-import:R0603")
      (libsource (lib "eagle-import") (part "R-US_R0603"))
    )
    (comp (ref "R74")
      (value "66.50k")
      (footprint "eagle-import:R0603")
      (libsource (lib "eagle-import") (part "R-US_R0603"))
    )
    (comp (ref "R75")
      (value "1.2k")
      (footprint "eagle-import:R0603")
      (libsource (lib "eagle-import") (part "R-US_R0603"))
    )
    (comp (ref "R76")
      (value "100.0k")
      (footprint "eagle-import:R0603")
      (libsource (lib "eagle-import") (part "R-US_R0603"))
    )
    (comp (ref "R77")
      (value "1.0M")
      (footprint "eagle-import:R0603")
      (libsource (lib "eagle-import") (part "R-US_R0603"))
    )
    (comp (ref "R78")
      (value "100.0k")
      (footprint "eagle-import:R0603")
      (libsource (lib "eagle-import") (part "R-US_R0603"))
    )
    (comp (ref "R79")
      (value "100.0k")
      (footprint "eagle-import:R0603")
      (libsource (lib "eagle-import") (part "R-US_R0603"))
    )
    (comp (ref "R80")
      (value "1.2k")
      (footprint "eagle-import:R0603")
      (libsource (lib "eagle-import") (part "R-US_R0603"))
    )
    (comp (ref "R81")
      (value "1.0M")
      (footprint "eagle-import:R0603")
      (libsource (lib "eagle-import") (part "R-US_R0603"))
    )
    (comp (ref "R82")
      (value "66.50k")
      (footprint "eagle-import:R0603")
      (libsource (lib "eagle-import") (part "R-US_R0603"))
    )
    (comp (ref "R83")
      (value "33.20k")
      (footprint "eagle-import:R0603")
      (libsource (lib "eagle-import") (part "R-US_R0603"))
    )
    (comp (ref "R84")
      (value "402")
      (footprint "eagle-import:R0603")
      (libsource (lib "eagle-import") (part "R-US_R0603"))
    )
    (comp (ref "R85")
      (value "1.0M")
      (footprint "eagle-import:R0603")
      (libsource (lib "eagle-import") (part "R-US_R0603"))
    )
    (comp (ref "R87")
      (value "510")
      (footprint "eagle-import:R0603")
      (libsource (lib "eagle-import") (part "R-US_R0603"))
    )
    (comp (ref "R88")
      (value "510")
      (footprint "eagle-import:R0603")
      (libsource (lib "eagle-import") (part "R-US_R0603"))
    )
    (comp (ref "R89")
      (value "100.0k")
      (footprint "eagle-import:R0603")
      (libsource (lib "eagle-import") (part "R-US_R0603"))
    )
    (comp (ref "R90")
      (value "33.20k")
      (footprint "eagle-import:R0603")
      (libsource (lib "eagle-import") (part "R-US_R0603"))
    )
  )
  (nets
    (net (code "1") (name "1_TO_2") (class "Default")
      (node (ref "IC1") (pin "14") (pinfunction "OUT_14") (pintype "output"))
      (node (ref "R56") (pin "2") (pinfunction "2_2") (pintype "passive"))
      (node (ref "R8") (pin "1") (pinfunction "1_1") (pintype "passive"))
    )
    (net (code "2") (name "2_TO_3") (class "Default")
      (node (ref "IC4") (pin "14") (pinfunction "OUT_14") (pintype "output"))
      (node (ref "R41") (pin "1") (pinfunction "1_1") (pintype "passive"))
      (node (ref "R82") (pin "2") (pinfunction "2_2") (pintype "passive"))
    )
    (net (code "3") (name "3_TO_4") (class "Default")
      (node (ref "IC8") (pin "14") (pinfunction "OUT_14") (pintype "output"))
      (node (ref "R114") (pin "2") (pinfunction "2_2") (pintype "passive"))
      (node (ref "R68") (pin "1") (pinfunction "1_1") (pintype "passive"))
    )
    (net (code "4") (name "AREF_+10") (class "Default")
      (node (ref "C26") (pin "1") (pinfunction "1_1") (pintype "passive"))
      (node (ref "C28") (pin "1") (pinfunction "1_1") (pintype "passive"))
      (node (ref "C3") (pin "1") (pinfunction "1_1") (pintype "passive"))
      (node (ref "IC6") (pin "1") (pinfunction "C_1") (pintype "passive"))
      (node (ref "R1") (pin "2") (pinfunction "2_2") (pintype "passive"))
      (node (ref "R101") (pin "2") (pinfunction "2_2") (pintype "passive"))
      (node (ref "R117") (pin "2") (pinfunction "2_2") (pintype "passive"))
      (node (ref "R20") (pin "2") (pinfunction "2_2") (pintype "passive"))
      (node (ref "R3") (pin "1") (pinfunction "1_1") (pintype "passive"))
      (node (ref "R34") (pin "1") (pinfunction "1_1") (pintype "passive"))
      (node (ref "R38") (pin "2") (pinfunction "2_2") (pintype "passive"))
      (node (ref "R57") (pin "2") (pinfunction "2_2") (pintype "passive"))
      (node (ref "R59") (pin "2") (pinfunction "2_2") (pintype "passive"))
      (node (ref "R61") (pin "2") (pinfunction "2_2") (pintype "passive"))
      (node (ref "R63") (pin "1") (pinfunction "1_1") (pintype "passive"))
      (node (ref "R79") (pin "2") (pinfunction "2_2") (pintype "passive"))
      (node (ref "R95") (pin "1") (pinfunction "1_1") (pintype "passive"))
    )
    (net (code "5") (name "AREF_-10") (class "Default")
      (node (ref "C27") (pin "1") (pinfunction "1_1") (pintype "passive"))
      (node (ref "IC7") (pin "2") (pinfunction "A_2") (pintype "passive"))
      (node (ref "R109") (pin "2") (pinfunction "2_2") (pintype "passive"))
      (node (ref "R16") (pin "2") (pinfunction "2_2") (pintype "passive"))
      (node (ref "R28") (pin "2") (pinfunction "2_2") (pintype "passive"))
      (node (ref "R31") (pin "2") (pinfunction "2_2") (pintype "passive"))
      (node (ref "R49") (pin "2") (pinfunction "2_2") (pintype "passive"))
      (node (ref "R60") (pin "2") (pinfunction "2_2") (pintype "passive"))
      (node (ref "R76") (pin "2") (pinfunction "2_2") (pintype "passive"))
      (node (ref "R89") (pin "2") (pinfunction "2_2") (pintype "passive"))
      (node (ref "R92") (pin "2") (pinfunction "2_2") (pintype "passive"))
    )
    (net (code "6") (name "GND") (class "Default")
      (node (ref "C1") (pin "+") (pinfunction "+_+") (pintype "passive"))
      (node (ref "C11") (pin "2") (pinfunction "2_2") (pintype "passive"))
      (node (ref "C12") (pin "2") (pinfunction "2_2") (pintype "passive"))
      (node (ref "C13") (pin "2") (pinfunction "2_2") (pintype "passive"))
      (node (ref "C14") (pin "2") (pinfunction "2_2") (pintype "passive"))
      (node (ref "C15") (pin "2") (pinfunction "2_2") (pintype "passive"))
      (node (ref "C16") (pin "1") (pinfunction "1_1") (pintype "passive"))
      (node (ref "C17") (pin "1") (pinfunction "1_1") (pintype "passive"))
      (node (ref "C18") (pin "2") (pinfunction "2_2") (pintype "passive"))
      (node (ref "C2") (pin "-") (pinfunction "-_-") (pintype "passive"))
      (node (ref "C21") (pin "2") (pinfunction "2_2") (pintype "passive"))
      (node (ref "C22") (pin "1") (pinfunction "1_1") (pintype "passive"))
      (node (ref "C24") (pin "2") (pinfunction "2_2") (pintype "passive"))
      (node (ref "C25") (pin "2") (pinfunction "2_2") (pintype "passive"))
      (node (ref "C26") (pin "2") (pinfunction "2_2") (pintype "passive"))
      (node (ref "C27") (pin "2") (pinfunction "2_2") (pintype "passive"))
      (node (ref "C28") (pin "2") (pinfunction "2_2") (pintype "passive"))
      (node (ref "C29") (pin "1") (pinfunction "1_1") (pintype "passive"))
      (node (ref "C3") (pin "2") (pinfunction "2_2") (pintype "passive"))
      (node (ref "C30") (pin "2") (pinfunction "2_2") (pintype "passive"))
      (node (ref "C32") (pin "2") (pinfunction "2_2") (pintype "passive"))
      (node (ref "C33") (pin "1") (pinfunction "1_1") (pintype "passive"))
      (node (ref "C36") (pin "2") (pinfunction "2_2") (pintype "passive"))
      (node (ref "C37") (pin "2") (pinfunction "2_2") (pintype "passive"))
      (node (ref "C38") (pin "2") (pinfunction "2_2") (pintype "passive"))
      (node (ref "C39") (pin "2") (pinfunction "2_2") (pintype "passive"))
      (node (ref "C4") (pin "1") (pinfunction "1_1") (pintype "passive"))
      (node (ref "C40") (pin "2") (pinfunction "2_2") (pintype "passive"))
      (node (ref "C41") (pin "1") (pinfunction "1_1") (pintype "passive"))
      (node (ref "C42") (pin "1") (pinfunction "1_1") (pintype "passive"))
      (node (ref "C43") (pin "2") (pinfunction "2_2") (pintype "passive"))
      (node (ref "C46") (pin "2") (pinfunction "2_2") (pintype "passive"))
      (node (ref "C47") (pin "1") (pinfunction "1_1") (pintype "passive"))
      (node (ref "C5") (pin "2") (pinfunction "2_2") (pintype "passive"))
      (node (ref "C7") (pin "2") (pinfunction "2_2") (pintype "passive"))
      (node (ref "C8") (pin "1") (pinfunction "1_1") (pintype "passive"))
      (node (ref "D1") (pin "C") (pinfunction "C_C") (pintype "passive"))
      (node (ref "IC1") (pin "12") (pinfunction "+IN_12") (pintype "input"))
      (node (ref "IC1") (pin "3") (pinfunction "+IN_3") (pintype "input"))
      (node (ref "IC1") (pin "5") (pinfunction "+IN_5") (pintype "input"))
      (node (ref "IC10") (pin "8") (pinfunction "GND_8") (pintype "power_in"))
      (node (ref "IC11") (pin "12") (pinfunction "+IN_12") (pintype "input"))
      (node (ref "IC11") (pin "3") (pinfunction "+IN_3") (pintype "input"))
      (node (ref "IC11") (pin "5") (pinfunction "+IN_5") (pintype "input"))
      (node (ref "IC12") (pin "12") (pinfunction "+IN_12") (pintype "input"))
      (node (ref "IC12") (pin "3") (pinfunction "+IN_3") (pintype "input"))
      (node (ref "IC12") (pin "5") (pinfunction "+IN_5") (pintype "input"))
      (node (ref "IC2") (pin "12") (pinfunction "+IN_12") (pintype "input"))
      (node (ref "IC2") (pin "3") (pinfunction "+IN_3") (pintype "input"))
      (node (ref "IC2") (pin "5") (pinfunction "+IN_5") (pintype "input"))
      (node (ref "IC3") (pin "8") (pinfunction "GND_8") (pintype "power_in"))
      (node (ref "IC4") (pin "12") (pinfunction "+IN_12") (pintype "input"))
      (node (ref "IC4") (pin "3") (pinfunction "+IN_3") (pintype "input"))
      (node (ref "IC4") (pin "5") (pinfunction "+IN_5") (pintype "input"))
      (node (ref "IC5") (pin "12") (pinfunction "+IN_12") (pintype "input"))
      (node (ref "IC5") (pin "3") (pinfunction "+IN_3") (pintype "input"))
      (node (ref "IC5") (pin "5") (pinfunction "+IN_5") (pintype "input"))
      (node (ref "IC6") (pin "2") (pinfunction "A_2") (pintype "passive"))
      (node (ref "IC7") (pin "1") (pinfunction "C_1") (pintype "passive"))
      (node (ref "IC8") (pin "12") (pinfunction "+IN_12") (pintype "input"))
      (node (ref "IC8") (pin "3") (pinfunction "+IN_3") (pintype "input"))
      (node (ref "IC8") (pin "5") (pinfunction "+IN_5") (pintype "input"))
      (node (ref "IC9") (pin "12") (pinfunction "+IN_12") (pintype "input"))
      (node (ref "IC9") (pin "3") (pinfunction "+IN_3") (pintype "input"))
      (node (ref "IC9") (pin "5") (pinfunction "+IN_5") (pintype "input"))
      (node (ref "J1") (pin "P1") (pinfunction "1_P1") (pintype "passive"))
      (node (ref "J10") (pin "P1") (pinfunction "1_P1") (pintype "passive"))
      (node (ref "J11") (pin "P1") (pinfunction "1_P1") (pintype "passive"))
      (node (ref "J12") (pin "P1") (pinfunction "1_P1") (pintype "passive"))
      (node (ref "J12") (pin "P2") (pinfunction "2_P2") (pintype "passive"))
      (node (ref "J2") (pin "P1") (pinfunction "1_P1") (pintype "passive"))
      (node (ref "J3") (pin "P1") (pinfunction "1_P1") (pintype "passive"))
      (node (ref "J3") (pin "P2") (pinfunction "2_P2") (pintype "passive"))
      (node (ref "J4") (pin "P1") (pinfunction "1_P1") (pintype "passive"))
      (node (ref "J5") (pin "P1") (pinfunction "1_P1") (pintype "passive"))
      (node (ref "J6") (pin "P1") (pinfunction "1_P1") (pintype "passive"))
      (node (ref "J6") (pin "P2") (pinfunction "2_P2") (pintype "passive"))
      (node (ref "J7") (pin "P1") (pinfunction "1_P1") (pintype "passive"))
      (node (ref "J8") (pin "P1") (pinfunction "1_P1") (pintype "passive"))
      (node (ref "J9") (pin "P1") (pinfunction "1_P1") (pintype "passive"))
      (node (ref "J9") (pin "P2") (pinfunction "2_P2") (pintype "passive"))
      (node (ref "JP5") (pin "3") (pinfunction "3_3") (pintype "passive"))
      (node (ref "JP5") (pin "4") (pinfunction "4_4") (pintype "passive"))
      (node (ref "JP5") (pin "5") (pinfunction "5_5") (pintype "passive"))
      (node (ref "JP5") (pin "6") (pinfunction "6_6") (pintype "passive"))
      (node (ref "JP5") (pin "7") (pinfunction "7_7") (pintype "passive"))
      (node (ref "JP5") (pin "8") (pinfunction "8_8") (pintype "passive"))
      (node (ref "R108") (pin "2") (pinfunction "2_2") (pintype "passive"))
      (node (ref "R110") (pin "2") (pinfunction "2_2") (pintype "passive"))
      (node (ref "R113") (pin "2") (pinfunction "2_2") (pintype "passive"))
      (node (ref "R12") (pin "2") (pinfunction "2_2") (pintype "passive"))
      (node (ref "R15") (pin "2") (pinfunction "2_2") (pintype "passive"))
      (node (ref "R18") (pin "2") (pinfunction "2_2") (pintype "passive"))
      (node (ref "R21") (pin "2") (pinfunction "2_2") (pintype "passive"))
      (node (ref "R35") (pin "2") (pinfunction "2_2") (pintype "passive"))
      (node (ref "R36") (pin "P$3") (pinfunction "A_P$3") (pintype "passive"))
      (node (ref "R4") (pin "P$3") (pinfunction "A_P$3") (pintype "passive"))
      (node (ref "R48") (pin "2") (pinfunction "2_2") (pintype "passive"))
      (node (ref "R52") (pin "2") (pinfunction "2_2") (pintype "passive"))
      (node (ref "R53") (pin "2") (pinfunction "2_2") (pintype "passive"))
      (node (ref "R64") (pin "P$3") (pinfunction "A_P$3") (pintype "passive"))
      (node (ref "R72") (pin "2") (pinfunction "2_2") (pintype "passive"))
      (node (ref "R75") (pin "2") (pinfunction "2_2") (pintype "passive"))
      (node (ref "R77") (pin "2") (pinfunction "2_2") (pintype "passive"))
      (node (ref "R80") (pin "2") (pinfunction "2_2") (pintype "passive"))
      (node (ref "R96") (pin "2") (pinfunction "2_2") (pintype "passive"))
      (node (ref "R97") (pin "P$3") (pinfunction "A_P$3") (pintype "passive"))
    )
    (net (code "7") (name "Net-(C12-Pad1)") (class "Default")
      (node (ref "C12") (pin "1") (pinfunction "1_1") (pintype "passive"))
      (node (ref "R26") (pin "1") (pinfunction "1_1") (pintype "passive"))
    )
    (net (code "8") (name "Net-(C13-Pad1)") (class "Default")
      (node (ref "C13") (pin "1") (pinfunction "1_1") (pintype "passive"))
      (node (ref "R27") (pin "1") (pinfunction "1_1") (pintype "passive"))
    )
    (net (code "9") (name "Net-(C14-Pad1)") (class "Default")
      (node (ref "C14") (pin "1") (pinfunction "1_1") (pintype "passive"))
      (node (ref "R33") (pin "1") (pinfunction "1_1") (pintype "passive"))
    )
    (net (code "10") (name "Net-(C15-Pad1)") (class "Default")
      (node (ref "C15") (pin "1") (pinfunction "1_1") (pintype "passive"))
      (node (ref "R32") (pin "1") (pinfunction "1_1") (pintype "passive"))
    )
    (net (code "11") (name "Net-(C37-Pad1)") (class "Default")
      (node (ref "C37") (pin "1") (pinfunction "1_1") (pintype "passive"))
      (node (ref "R87") (pin "1") (pinfunction "1_1") (pintype "passive"))
    )
    (net (code "12") (name "Net-(C38-Pad1)") (class "Default")
      (node (ref "C38") (pin "1") (pinfunction "1_1") (pintype "passive"))
      (node (ref "R88") (pin "1") (pinfunction "1_1") (pintype "passive"))
    )
    (net (code "13") (name "Net-(C39-Pad1)") (class "Default")
      (node (ref "C39") (pin "1") (pinfunction "1_1") (pintype "passive"))
      (node (ref "R94") (pin "1") (pinfunction "1_1") (pintype "passive"))
    )
    (net (code "14") (name "Net-(C40-Pad1)") (class "Default")
      (node (ref "C40") (pin "1") (pinfunction "1_1") (pintype "passive"))
      (node (ref "R93") (pin "1") (pinfunction "1_1") (pintype "passive"))
    )
    (net (code "15") (name "Net-(D2-PadA)") (class "Default")
      (node (ref "D2") (pin "A") (pinfunction "A_A") (pintype "passive"))
      (node (ref "JP5") (pin "1") (pinfunction "1_1") (pintype "passive"))
      (node (ref "JP5") (pin "2") (pinfunction "2_2") (pintype "passive"))
    )
    (net (code "16") (name "Net-(D2-PadC)") (class "Default")
      (node (ref "D2") (pin "C") (pinfunction "C_C") (pintype "passive"))
      (node (ref "L1") (pin "2") (pinfunction "2_2") (pintype "passive"))
    )
    (net (code "17") (name "Net-(IC1A--IN)") (class "Default")
      (node (ref "IC1") (pin "2") (pinfunction "-IN_2") (pintype "input"))
      (node (ref "IC3") (pin "13") (pinfunction "OUT_13") (pintype "output"))
      (node (ref "R7") (pin "2") (pinfunction "2_2") (pintype "passive"))
    )
    (net (code "18") (name "Net-(IC1A-OUT)") (class "Default")
      (node (ref "IC1") (pin "1") (pinfunction "OUT_1") (pintype "output"))
      (node (ref "R13") (pin "2") (pinfunction "2_2") (pintype "passive"))
      (node (ref "R7") (pin "1") (pinfunction "1_1") (pintype "passive"))
    )
    (net (code "19") (name "Net-(IC1B--IN)") (class "Default")
      (node (ref "C9") (pin "1") (pinfunction "1_1") (pintype "passive"))
      (node (ref "IC1") (pin "6") (pinfunction "-IN_6") (pintype "input"))
      (node (ref "R13") (pin "1") (pinfunction "1_1") (pintype "passive"))
      (node (ref "R14") (pin "2") (pinfunction "2_2") (pintype "passive"))
      (node (ref "R23") (pin "1") (pinfunction "1_1") (pintype "passive"))
    )
    (net (code "20") (name "Net-(IC1B-OUT)") (class "Default")
      (node (ref "C9") (pin "2") (pinfunction "2_2") (pintype "passive"))
      (node (ref "IC1") (pin "7") (pinfunction "OUT_7") (pintype "output"))
      (node (ref "R14") (pin "1") (pinfunction "1_1") (pintype "passive"))
      (node (ref "R17") (pin "2") (pinfunction "2_2") (pintype "passive"))
      (node (ref "R24") (pin "2") (pinfunction "2_2") (pintype "passive"))
    )
    (net (code "21") (name "Net-(IC1C-+IN)") (class "Default")
      (node (ref "IC1") (pin "10") (pinfunction "+IN_10") (pintype "input"))
      (node (ref "R18") (pin "1") (pinfunction "1_1") (pintype "passive"))
      (node (ref "R24") (pin "1") (pinfunction "1_1") (pintype "passive"))
    )
    (net (code "22") (name "Net-(IC1C--IN)") (class "Default")
      (node (ref "IC1") (pin "9") (pinfunction "-IN_9") (pintype "input"))
      (node (ref "LED1") (pin "A") (pinfunction "A_A") (pintype "passive"))
      (node (ref "R15") (pin "1") (pinfunction "1_1") (pintype "passive"))
    )
    (net (code "23") (name "Net-(IC1C-OUT)") (class "Default")
      (node (ref "IC1") (pin "8") (pinfunction "OUT_8") (pintype "output"))
      (node (ref "LED1") (pin "K") (pinfunction "C_K") (pintype "passive"))
    )
    (net (code "24") (name "Net-(IC1D--IN)") (class "Default")
      (node (ref "IC1") (pin "13") (pinfunction "-IN_13") (pintype "input"))
      (node (ref "R10") (pin "1") (pinfunction "1_1") (pintype "passive"))
      (node (ref "R8") (pin "2") (pinfunction "2_2") (pintype "passive"))
    )
    (net (code "25") (name "Net-(IC2A--IN)") (class "Default")
      (node (ref "C6") (pin "2") (pinfunction "2_2") (pintype "passive"))
      (node (ref "IC2") (pin "2") (pinfunction "-IN_2") (pintype "input"))
      (node (ref "R1") (pin "1") (pinfunction "1_1") (pintype "passive"))
      (node (ref "R2") (pin "1") (pinfunction "1_1") (pintype "passive"))
      (node (ref "R4") (pin "P$1") (pinfunction "E_P$1") (pintype "passive"))
      (node (ref "R5") (pin "P$3") (pinfunction "A_P$3") (pintype "passive"))
      (node (ref "R6") (pin "2") (pinfunction "2_2") (pintype "passive"))
    )
    (net (code "26") (name "Net-(IC2A-OUT)") (class "Default")
      (node (ref "C6") (pin "1") (pinfunction "1_1") (pintype "passive"))
      (node (ref "IC2") (pin "1") (pinfunction "OUT_1") (pintype "output"))
      (node (ref "R22") (pin "2") (pinfunction "2_2") (pintype "passive"))
      (node (ref "R23") (pin "2") (pinfunction "2_2") (pintype "passive"))
      (node (ref "R29") (pin "2") (pinfunction "2_2") (pintype "passive"))
      (node (ref "R6") (pin "1") (pinfunction "1_1") (pintype "passive"))
    )
    (net (code "27") (name "Net-(IC2B--IN)") (class "Default")
      (node (ref "C10") (pin "1") (pinfunction "1_1") (pintype "passive"))
      (node (ref "IC2") (pin "6") (pinfunction "-IN_6") (pintype "input"))
      (node (ref "IC3") (pin "4") (pinfunction "OUT_4") (pintype "output"))
      (node (ref "R19") (pin "1") (pinfunction "1_1") (pintype "passive"))
      (node (ref "R20") (pin "1") (pinfunction "1_1") (pintype "passive"))
    )
    (net (code "28") (name "Net-(IC2B-OUT)") (class "Default")
      (node (ref "C10") (pin "2") (pinfunction "2_2") (pintype "passive"))
      (node (ref "IC2") (pin "7") (pinfunction "OUT_7") (pintype "output"))
      (node (ref "IC3") (pin "14") (pinfunction "CTRL_14") (pintype "input"))
      (node (ref "IC3") (pin "3") (pinfunction "CTRL_3") (pintype "input"))
    )
    (net (code "29") (name "Net-(IC2C-+IN)") (class "Default")
      (node (ref "IC2") (pin "10") (pinfunction "+IN_10") (pintype "input"))
      (node (ref "R12") (pin "1") (pinfunction "1_1") (pintype "passive"))
      (node (ref "R22") (pin "1") (pinfunction "1_1") (pintype "passive"))
    )
    (net (code "30") (name "Net-(IC2C--IN)") (class "Default")
      (node (ref "IC2") (pin "9") (pinfunction "-IN_9") (pintype "input"))
      (node (ref "LED2") (pin "A") (pinfunction "A_A") (pintype "passive"))
      (node (ref "R21") (pin "1") (pinfunction "1_1") (pintype "passive"))
    )
    (net (code "31") (name "Net-(IC2C-OUT)") (class "Default")
      (node (ref "IC2") (pin "8") (pinfunction "OUT_8") (pintype "output"))
      (node (ref "LED2") (pin "K") (pinfunction "C_K") (pintype "passive"))
    )
    (net (code "32") (name "Net-(IC2D--IN)") (class "Default")
      (node (ref "IC2") (pin "13") (pinfunction "-IN_13") (pintype "input"))
      (node (ref "R5") (pin "P$1") (pinfunction "E_P$1") (pintype "passive"))
      (node (ref "R9") (pin "2") (pinfunction "2_2") (pintype "passive"))
    )
    (net (code "33") (name "Net-(IC2D-OUT)") (class "Default")
      (node (ref "IC2") (pin "14") (pinfunction "OUT_14") (pintype "output"))
      (node (ref "R2") (pin "2") (pinfunction "2_2") (pintype "passive"))
      (node (ref "R9") (pin "1") (pinfunction "1_1") (pintype "passive"))
    )
    (net (code "34") (name "Net-(IC3A-IN)") (class "Default")
      (node (ref "IC3") (pin "2") (pinfunction "IN_2") (pintype "input"))
      (node (ref "R27") (pin "2") (pinfunction "2_2") (pintype "passive"))
      (node (ref "R28") (pin "1") (pinfunction "1_1") (pintype "passive"))
    )
    (net (code "35") (name "Net-(IC3B-CTRL)") (class "Default")
      (node (ref "C19") (pin "2") (pinfunction "2_2") (pintype "passive"))
      (node (ref "IC3") (pin "11") (pinfunction "CTRL_11") (pintype "input"))
      (node (ref "IC3") (pin "6") (pinfunction "CTRL_6") (pintype "input"))
      (node (ref "IC5") (pin "1") (pinfunction "OUT_1") (pintype "output"))
    )
    (net (code "36") (name "Net-(IC3B-IN)") (class "Default")
      (node (ref "IC3") (pin "7") (pinfunction "IN_7") (pintype "input"))
      (node (ref "R31") (pin "1") (pinfunction "1_1") (pintype "passive"))
      (node (ref "R33") (pin "2") (pinfunction "2_2") (pintype "passive"))
    )
    (net (code "37") (name "Net-(IC3B-OUT)") (class "Default")
      (node (ref "C19") (pin "1") (pinfunction "1_1") (pintype "passive"))
      (node (ref "IC3") (pin "5") (pinfunction "OUT_5") (pintype "output"))
      (node (ref "IC5") (pin "2") (pinfunction "-IN_2") (pintype "input"))
      (node (ref "R38") (pin "1") (pinfunction "1_1") (pintype "passive"))
      (node (ref "R39") (pin "1") (pinfunction "1_1") (pintype "passive"))
    )
    (net (code "38") (name "Net-(IC3C-IN)") (class "Default")
      (node (ref "IC3") (pin "10") (pinfunction "IN_10") (pintype "input"))
      (node (ref "R30") (pin "1") (pinfunction "1_1") (pintype "passive"))
      (node (ref "R32") (pin "2") (pinfunction "2_2") (pintype "passive"))
    )
    (net (code "39") (name "Net-(IC3C-OUT)") (class "Default")
      (node (ref "IC3") (pin "12") (pinfunction "OUT_12") (pintype "output"))
      (node (ref "IC4") (pin "2") (pinfunction "-IN_2") (pintype "input"))
      (node (ref "R40") (pin "2") (pinfunction "2_2") (pintype "passive"))
    )
    (net (code "40") (name "Net-(IC3D-IN)") (class "Default")
      (node (ref "IC3") (pin "15") (pinfunction "IN_15") (pintype "input"))
      (node (ref "R26") (pin "2") (pinfunction "2_2") (pintype "passive"))
      (node (ref "R29") (pin "1") (pinfunction "1_1") (pintype "passive"))
    )
    (net (code "41") (name "Net-(IC3E-MODE)") (class "Default")
      (node (ref "IC3") (pin "1") (pinfunction "MODE_1") (pintype "input"))
      (node (ref "R25") (pin "2") (pinfunction "2_2") (pintype "passive"))
    )
    (net (code "42") (name "Net-(IC4A-OUT)") (class "Default")
      (node (ref "IC4") (pin "1") (pinfunction "OUT_1") (pintype "output"))
      (node (ref "R40") (pin "1") (pinfunction "1_1") (pintype "passive"))
      (node (ref "R46") (pin "2") (pinfunction "2_2") (pintype "passive"))
    )
    (net (code "43") (name "Net-(IC4B--IN)") (class "Default")
      (node (ref "C20") (pin "1") (pinfunction "1_1") (pintype "passive"))
      (node (ref "IC4") (pin "6") (pinfunction "-IN_6") (pintype "input"))
      (node (ref "R46") (pin "1") (pinfunction "1_1") (pintype "passive"))
      (node (ref "R47") (pin "2") (pinfunction "2_2") (pintype "passive"))
      (node (ref "R54") (pin "1") (pinfunction "1_1") (pintype "passive"))
      (node (ref "R56") (pin "1") (pinfunction "1_1") (pintype "passive"))
    )
    (net (code "44") (name "Net-(IC4B-OUT)") (class "Default")
      (node (ref "C20") (pin "2") (pinfunction "2_2") (pintype "passive"))
      (node (ref "IC4") (pin "7") (pinfunction "OUT_7") (pintype "output"))
      (node (ref "R47") (pin "1") (pinfunction "1_1") (pintype "passive"))
      (node (ref "R55") (pin "2") (pinfunction "2_2") (pintype "passive"))
      (node (ref "R58") (pin "2") (pinfunction "2_2") (pintype "passive"))
    )
    (net (code "45") (name "Net-(IC4C-+IN)") (class "Default")
      (node (ref "IC4") (pin "10") (pinfunction "+IN_10") (pintype "input"))
      (node (ref "R52") (pin "1") (pinfunction "1_1") (pintype "passive"))
      (node (ref "R58") (pin "1") (pinfunction "1_1") (pintype "passive"))
    )
    (net (code "46") (name "Net-(IC4C--IN)") (class "Default")
      (node (ref "IC4") (pin "9") (pinfunction "-IN_9") (pintype "input"))
      (node (ref "LED3") (pin "A") (pinfunction "A_A") (pintype "passive"))
      (node (ref "R48") (pin "1") (pinfunction "1_1") (pintype "passive"))
    )
    (net (code "47") (name "Net-(IC4C-OUT)") (class "Default")
      (node (ref "IC4") (pin "8") (pinfunction "OUT_8") (pintype "output"))
      (node (ref "LED3") (pin "K") (pinfunction "C_K") (pintype "passive"))
    )
    (net (code "48") (name "Net-(IC4D--IN)") (class "Default")
      (node (ref "IC4") (pin "13") (pinfunction "-IN_13") (pintype "input"))
      (node (ref "R41") (pin "2") (pinfunction "2_2") (pintype "passive"))
      (node (ref "R44") (pin "1") (pinfunction "1_1") (pintype "passive"))
    )
    (net (code "49") (name "Net-(IC5B--IN)") (class "Default")
      (node (ref "C23") (pin "2") (pinfunction "2_2") (pintype "passive"))
      (node (ref "IC5") (pin "6") (pinfunction "-IN_6") (pintype "input"))
      (node (ref "R36") (pin "P$1") (pinfunction "E_P$1") (pintype "passive"))
      (node (ref "R37") (pin "P$3") (pinfunction "A_P$3") (pintype "passive"))
      (node (ref "R50") (pin "1") (pinfunction "1_1") (pintype "passive"))
      (node (ref "R51") (pin "2") (pinfunction "2_2") (pintype "passive"))
      (node (ref "R57") (pin "1") (pinfunction "1_1") (pintype "passive"))
    )
    (net (code "50") (name "Net-(IC5B-OUT)") (class "Default")
      (node (ref "C23") (pin "1") (pinfunction "1_1") (pintype "passive"))
      (node (ref "IC5") (pin "7") (pinfunction "OUT_7") (pintype "output"))
      (node (ref "R30") (pin "2") (pinfunction "2_2") (pintype "passive"))
      (node (ref "R42") (pin "2") (pinfunction "2_2") (pintype "passive"))
      (node (ref "R51") (pin "1") (pinfunction "1_1") (pintype "passive"))
      (node (ref "R54") (pin "2") (pinfunction "2_2") (pintype "passive"))
    )
    (net (code "51") (name "Net-(IC5C-+IN)") (class "Default")
      (node (ref "IC5") (pin "10") (pinfunction "+IN_10") (pintype "input"))
      (node (ref "R35") (pin "1") (pinfunction "1_1") (pintype "passive"))
      (node (ref "R42") (pin "1") (pinfunction "1_1") (pintype "passive"))
    )
    (net (code "52") (name "Net-(IC5C--IN)") (class "Default")
      (node (ref "IC5") (pin "9") (pinfunction "-IN_9") (pintype "input"))
      (node (ref "LED4") (pin "A") (pinfunction "A_A") (pintype "passive"))
      (node (ref "R53") (pin "1") (pinfunction "1_1") (pintype "passive"))
    )
    (net (code "53") (name "Net-(IC5C-OUT)") (class "Default")
      (node (ref "IC5") (pin "8") (pinfunction "OUT_8") (pintype "output"))
      (node (ref "LED4") (pin "K") (pinfunction "C_K") (pintype "passive"))
    )
    (net (code "54") (name "Net-(IC5D--IN)") (class "Default")
      (node (ref "IC5") (pin "13") (pinfunction "-IN_13") (pintype "input"))
      (node (ref "R37") (pin "P$1") (pinfunction "E_P$1") (pintype "passive"))
      (node (ref "R43") (pin "2") (pinfunction "2_2") (pintype "passive"))
    )
    (net (code "55") (name "Net-(IC5D-OUT)") (class "Default")
      (node (ref "IC5") (pin "14") (pinfunction "OUT_14") (pintype "output"))
      (node (ref "R43") (pin "1") (pinfunction "1_1") (pintype "passive"))
      (node (ref "R50") (pin "2") (pinfunction "2_2") (pintype "passive"))
    )
    (net (code "56") (name "Net-(IC8A-OUT)") (class "Default")
      (node (ref "IC8") (pin "1") (pinfunction "OUT_1") (pintype "output"))
      (node (ref "R67") (pin "1") (pinfunction "1_1") (pintype "passive"))
      (node (ref "R73") (pin "2") (pinfunction "2_2") (pintype "passive"))
    )
    (net (code "57") (name "Net-(IC8B--IN)") (class "Default")
      (node (ref "C34") (pin "1") (pinfunction "1_1") (pintype "passive"))
      (node (ref "IC8") (pin "6") (pinfunction "-IN_6") (pintype "input"))
      (node (ref "R73") (pin "1") (pinfunction "1_1") (pintype "passive"))
      (node (ref "R74") (pin "2") (pinfunction "2_2") (pintype "passive"))
      (node (ref "R82") (pin "1") (pinfunction "1_1") (pintype "passive"))
      (node (ref "R83") (pin "1") (pinfunction "1_1") (pintype "passive"))
    )
    (net (code "58") (name "Net-(IC8B-OUT)") (class "Default")
      (node (ref "C34") (pin "2") (pinfunction "2_2") (pintype "passive"))
      (node (ref "IC8") (pin "7") (pinfunction "OUT_7") (pintype "output"))
      (node (ref "R74") (pin "1") (pinfunction "1_1") (pintype "passive"))
      (node (ref "R84") (pin "2") (pinfunction "2_2") (pintype "passive"))
      (node (ref "R85") (pin "2") (pinfunction "2_2") (pintype "passive"))
    )
    (net (code "59") (name "Net-(IC8C-+IN)") (class "Default")
      (node (ref "IC8") (pin "10") (pinfunction "+IN_10") (pintype "input"))
      (node (ref "R77") (pin "1") (pinfunction "1_1") (pintype "passive"))
      (node (ref "R85") (pin "1") (pinfunction "1_1") (pintype "passive"))
    )
    (net (code "60") (name "Net-(IC8C--IN)") (class "Default")
      (node (ref "IC8") (pin "9") (pinfunction "-IN_9") (pintype "input"))
      (node (ref "LED5") (pin "A") (pinfunction "A_A") (pintype "passive"))
      (node (ref "R75") (pin "1") (pinfunction "1_1") (pintype "passive"))
    )
    (net (code "61") (name "Net-(IC8C-OUT)") (class "Default")
      (node (ref "IC8") (pin "8") (pinfunction "OUT_8") (pintype "output"))
      (node (ref "LED5") (pin "K") (pinfunction "C_K") (pintype "passive"))
    )
    (net (code "62") (name "Net-(IC8D--IN)") (class "Default")
      (node (ref "IC8") (pin "13") (pinfunction "-IN_13") (pintype "input"))
      (node (ref "R68") (pin "2") (pinfunction "2_2") (pintype "passive"))
      (node (ref "R70") (pin "1") (pinfunction "1_1") (pintype "passive"))
    )
    (net (code "63") (name "Net-(IC9A--IN)") (class "Default")
      (node (ref "C31") (pin "2") (pinfunction "2_2") (pintype "passive"))
      (node (ref "IC9") (pin "2") (pinfunction "-IN_2") (pintype "input"))
      (node (ref "R61") (pin "1") (pinfunction "1_1") (pintype "passive"))
      (node (ref "R62") (pin "1") (pinfunction "1_1") (pintype "passive"))
      (node (ref "R64") (pin "P$1") (pinfunction "E_P$1") (pintype "passive"))
      (node (ref "R65") (pin "P$3") (pinfunction "A_P$3") (pintype "passive"))
      (node (ref "R66") (pin "2") (pinfunction "2_2") (pintype "passive"))
    )
    (net (code "64") (name "Net-(IC9A-OUT)") (class "Default")
      (node (ref "C31") (pin "1") (pinfunction "1_1") (pintype "passive"))
      (node (ref "IC9") (pin "1") (pinfunction "OUT_1") (pintype "output"))
      (node (ref "R66") (pin "1") (pinfunction "1_1") (pintype "passive"))
      (node (ref "R81") (pin "2") (pinfunction "2_2") (pintype "passive"))
      (node (ref "R83") (pin "2") (pinfunction "2_2") (pintype "passive"))
      (node (ref "R90") (pin "2") (pinfunction "2_2") (pintype "passive"))
    )
    (net (code "65") (name "Net-(IC9C-+IN)") (class "Default")
      (node (ref "IC9") (pin "10") (pinfunction "+IN_10") (pintype "input"))
      (node (ref "R72") (pin "1") (pinfunction "1_1") (pintype "passive"))
      (node (ref "R81") (pin "1") (pinfunction "1_1") (pintype "passive"))
    )
    (net (code "66") (name "Net-(IC9C--IN)") (class "Default")
      (node (ref "IC9") (pin "9") (pinfunction "-IN_9") (pintype "input"))
      (node (ref "LED6") (pin "A") (pinfunction "A_A") (pintype "passive"))
      (node (ref "R80") (pin "1") (pinfunction "1_1") (pintype "passive"))
    )
    (net (code "67") (name "Net-(IC9C-OUT)") (class "Default")
      (node (ref "IC9") (pin "8") (pinfunction "OUT_8") (pintype "output"))
      (node (ref "LED6") (pin "K") (pinfunction "C_K") (pintype "passive"))
    )
    (net (code "68") (name "Net-(IC9D--IN)") (class "Default")
      (node (ref "IC9") (pin "13") (pinfunction "-IN_13") (pintype "input"))
      (node (ref "R65") (pin "P$1") (pinfunction "E_P$1") (pintype "passive"))
      (node (ref "R69") (pin "2") (pinfunction "2_2") (pintype "passive"))
    )
    (net (code "69") (name "Net-(IC9D-OUT)") (class "Default")
      (node (ref "IC9") (pin "14") (pinfunction "OUT_14") (pintype "output"))
      (node (ref "R62") (pin "2") (pinfunction "2_2") (pintype "passive"))
      (node (ref "R69") (pin "1") (pinfunction "1_1") (pintype "passive"))
    )
    (net (code "70") (name "Net-(IC10A-CTRL)") (class "Default")
      (node (ref "C35") (pin "2") (pinfunction "2_2") (pintype "passive"))
      (node (ref "IC10") (pin "14") (pinfunction "CTRL_14") (pintype "input"))
      (node (ref "IC10") (pin "3") (pinfunction "CTRL_3") (pintype "input"))
      (node (ref "IC9") (pin "7") (pinfunction "OUT_7") (pintype "output"))
    )
    (net (code "71") (name "Net-(IC10A-IN)") (class "Default")
      (node (ref "IC10") (pin "2") (pinfunction "IN_2") (pintype "input"))
      (node (ref "R88") (pin "2") (pinfunction "2_2") (pintype "passive"))
      (node (ref "R89") (pin "1") (pinfunction "1_1") (pintype "passive"))
    )
    (net (code "72") (name "Net-(IC10A-OUT)") (class "Default")
      (node (ref "C35") (pin "1") (pinfunction "1_1") (pintype "passive"))
      (node (ref "IC10") (pin "4") (pinfunction "OUT_4") (pintype "output"))
      (node (ref "IC9") (pin "6") (pinfunction "-IN_6") (pintype "input"))
      (node (ref "R78") (pin "1") (pinfunction "1_1") (pintype "passive"))
      (node (ref "R79") (pin "1") (pinfunction "1_1") (pintype "passive"))
    )
    (net (code "73") (name "Net-(IC10B-CTRL)") (class "Default")
      (node (ref "C44") (pin "2") (pinfunction "2_2") (pintype "passive"))
      (node (ref "IC10") (pin "11") (pinfunction "CTRL_11") (pintype "input"))
      (node (ref "IC10") (pin "6") (pinfunction "CTRL_6") (pintype "input"))
      (node (ref "IC12") (pin "1") (pinfunction "OUT_1") (pintype "output"))
    )
    (net (code "74") (name "Net-(IC10B-IN)") (class "Default")
      (node (ref "IC10") (pin "7") (pinfunction "IN_7") (pintype "input"))
      (node (ref "R92") (pin "1") (pinfunction "1_1") (pintype "passive"))
      (node (ref "R94") (pin "2") (pinfunction "2_2") (pintype "passive"))
    )
    (net (code "75") (name "Net-(IC10B-OUT)") (class "Default")
      (node (ref "C44") (pin "1") (pinfunction "1_1") (pintype "passive"))
      (node (ref "IC10") (pin "5") (pinfunction "OUT_5") (pintype "output"))
      (node (ref "IC12") (pin "2") (pinfunction "-IN_2") (pintype "input"))
      (node (ref "R101") (pin "1") (pinfunction "1_1") (pintype "passive"))
      (node (ref "R102") (pin "1") (pinfunction "1_1") (pintype "passive"))
    )
    (net (code "76") (name "Net-(IC10C-IN)") (class "Default")
      (node (ref "IC10") (pin "10") (pinfunction "IN_10") (pintype "input"))
      (node (ref "R91") (pin "1") (pinfunction "1_1") (pintype "passive"))
      (node (ref "R93") (pin "2") (pinfunction "2_2") (pintype "passive"))
    )
    (net (code "77") (name "Net-(IC10C-OUT)") (class "Default")
      (node (ref "IC10") (pin "12") (pinfunction "OUT_12") (pintype "output"))
      (node (ref "IC11") (pin "2") (pinfunction "-IN_2") (pintype "input"))
      (node (ref "R100") (pin "2") (pinfunction "2_2") (pintype "passive"))
    )
    (net (code "78") (name "Net-(IC10D-IN)") (class "Default")
      (node (ref "IC10") (pin "15") (pinfunction "IN_15") (pintype "input"))
      (node (ref "R87") (pin "2") (pinfunction "2_2") (pintype "passive"))
      (node (ref "R90") (pin "1") (pinfunction "1_1") (pintype "passive"))
    )
    (net (code "79") (name "Net-(IC10D-OUT)") (class "Default")
      (node (ref "IC10") (pin "13") (pinfunction "OUT_13") (pintype "output"))
      (node (ref "IC8") (pin "2") (pinfunction "-IN_2") (pintype "input"))
      (node (ref "R67") (pin "2") (pinfunction "2_2") (pintype "passive"))
    )
    (net (code "80") (name "Net-(IC10E-MODE)") (class "Default")
      (node (ref "IC10") (pin "1") (pinfunction "MODE_1") (pintype "input"))
      (node (ref "R86") (pin "2") (pinfunction "2_2") (pintype "passive"))
    )
    (net (code "81") (name "Net-(IC11A-OUT)") (class "Default")
      (node (ref "IC11") (pin "1") (pinfunction "OUT_1") (pintype "output"))
      (node (ref "R100") (pin "1") (pinfunction "1_1") (pintype "passive"))
      (node (ref "R99") (pin "2") (pinfunction "2_2") (pintype "passive"))
    )
    (net (code "82") (name "Net-(IC11B--IN)") (class "Default")
      (node (ref "C45") (pin "1") (pinfunction "1_1") (pintype "passive"))
      (node (ref "IC11") (pin "6") (pinfunction "-IN_6") (pintype "input"))
      (node (ref "R103") (pin "1") (pinfunction "1_1") (pintype "passive"))
      (node (ref "R107") (pin "2") (pinfunction "2_2") (pintype "passive"))
      (node (ref "R114") (pin "1") (pinfunction "1_1") (pintype "passive"))
      (node (ref "R99") (pin "1") (pinfunction "1_1") (pintype "passive"))
    )
    (net (code "83") (name "Net-(IC11B-OUT)") (class "Default")
      (node (ref "C45") (pin "2") (pinfunction "2_2") (pintype "passive"))
      (node (ref "IC11") (pin "7") (pinfunction "OUT_7") (pintype "output"))
      (node (ref "R107") (pin "1") (pinfunction "1_1") (pintype "passive"))
      (node (ref "R115") (pin "2") (pinfunction "2_2") (pintype "passive"))
      (node (ref "R116") (pin "2") (pinfunction "2_2") (pintype "passive"))
    )
    (net (code "84") (name "Net-(IC11C-+IN)") (class "Default")
      (node (ref "IC11") (pin "10") (pinfunction "+IN_10") (pintype "input"))
      (node (ref "R110") (pin "1") (pinfunction "1_1") (pintype "passive"))
      (node (ref "R115") (pin "1") (pinfunction "1_1") (pintype "passive"))
    )
    (net (code "85") (name "Net-(IC11C--IN)") (class "Default")
      (node (ref "IC11") (pin "9") (pinfunction "-IN_9") (pintype "input"))
      (node (ref "LED7") (pin "A") (pinfunction "A_A") (pintype "passive"))
      (node (ref "R108") (pin "1") (pinfunction "1_1") (pintype "passive"))
    )
    (net (code "86") (name "Net-(IC11C-OUT)") (class "Default")
      (node (ref "IC11") (pin "8") (pinfunction "OUT_8") (pintype "output"))
      (node (ref "LED7") (pin "K") (pinfunction "C_K") (pintype "passive"))
    )
    (net (code "87") (name "Net-(IC11D--IN)") (class "Default")
      (node (ref "IC11") (pin "13") (pinfunction "-IN_13") (pintype "input"))
      (node (ref "IC11") (pin "14") (pinfunction "OUT_14") (pintype "output"))
    )
    (net (code "88") (name "Net-(IC12B--IN)") (class "Default")
      (node (ref "C48") (pin "2") (pinfunction "2_2") (pintype "passive"))
      (node (ref "IC12") (pin "6") (pinfunction "-IN_6") (pintype "input"))
      (node (ref "R111") (pin "1") (pinfunction "1_1") (pintype "passive"))
      (node (ref "R112") (pin "2") (pinfunction "2_2") (pintype "passive"))
      (node (ref "R117") (pin "1") (pinfunction "1_1") (pintype "passive"))
      (node (ref "R97") (pin "P$1") (pinfunction "E_P$1") (pintype "passive"))
      (node (ref "R98") (pin "P$3") (pinfunction "A_P$3") (pintype "passive"))
    )
    (net (code "89") (name "Net-(IC12B-OUT)") (class "Default")
      (node (ref "C48") (pin "1") (pinfunction "1_1") (pintype "passive"))
      (node (ref "IC12") (pin "7") (pinfunction "OUT_7") (pintype "output"))
      (node (ref "R103") (pin "2") (pinfunction "2_2") (pintype "passive"))
      (node (ref "R104") (pin "2") (pinfunction "2_2") (pintype "passive"))
      (node (ref "R112") (pin "1") (pinfunction "1_1") (pintype "passive"))
      (node (ref "R91") (pin "2") (pinfunction "2_2") (pintype "passive"))
    )
    (net (code "90") (name "Net-(IC12C-+IN)") (class "Default")
      (node (ref "IC12") (pin "10") (pinfunction "+IN_10") (pintype "input"))
      (node (ref "R104") (pin "1") (pinfunction "1_1") (pintype "passive"))
      (node (ref "R96") (pin "1") (pinfunction "1_1") (pintype "passive"))
    )
    (net (code "91") (name "Net-(IC12C--IN)") (class "Default")
      (node (ref "IC12") (pin "9") (pinfunction "-IN_9") (pintype "input"))
      (node (ref "LED8") (pin "A") (pinfunction "A_A") (pintype "passive"))
      (node (ref "R113") (pin "1") (pinfunction "1_1") (pintype "passive"))
    )
    (net (code "92") (name "Net-(IC12C-OUT)") (class "Default")
      (node (ref "IC12") (pin "8") (pinfunction "OUT_8") (pintype "output"))
      (node (ref "LED8") (pin "K") (pinfunction "C_K") (pintype "passive"))
    )
    (net (code "93") (name "Net-(IC12D--IN)") (class "Default")
      (node (ref "IC12") (pin "13") (pinfunction "-IN_13") (pintype "input"))
      (node (ref "R105") (pin "2") (pinfunction "2_2") (pintype "passive"))
      (node (ref "R98") (pin "P$1") (pinfunction "E_P$1") (pintype "passive"))
    )
    (net (code "94") (name "Net-(IC12D-OUT)") (class "Default")
      (node (ref "IC12") (pin "14") (pinfunction "OUT_14") (pintype "output"))
      (node (ref "R105") (pin "1") (pinfunction "1_1") (pintype "passive"))
      (node (ref "R111") (pin "2") (pinfunction "2_2") (pintype "passive"))
    )
    (net (code "95") (name "Net-(J1-2)") (class "Default")
      (node (ref "J1") (pin "P2") (pinfunction "2_P2") (pintype "passive"))
      (node (ref "R3") (pin "2") (pinfunction "2_2") (pintype "passive"))
    )
    (net (code "96") (name "Net-(J1-3)") (class "Default")
      (node (ref "J1") (pin "P3") (pinfunction "3_P3") (pintype "passive"))
      (node (ref "R19") (pin "2") (pinfunction "2_2") (pintype "passive"))
    )
    (net (code "97") (name "Net-(J2-2)") (class "Default")
      (node (ref "J2") (pin "P2") (pinfunction "2_P2") (pintype "passive"))
      (node (ref "R10") (pin "2") (pinfunction "2_2") (pintype "passive"))
    )
    (net (code "98") (name "Net-(J2-3)") (class "Default")
      (node (ref "J2") (pin "P3") (pinfunction "3_P3") (pintype "passive"))
      (node (ref "R17") (pin "1") (pinfunction "1_1") (pintype "passive"))
    )
    (net (code "99") (name "Net-(J3-3)") (class "Default")
      (node (ref "J3") (pin "P3") (pinfunction "3_P3") (pintype "passive"))
      (node (ref "R11") (pin "2") (pinfunction "2_2") (pintype "passive"))
    )
    (net (code "100") (name "Net-(J4-2)") (class "Default")
      (node (ref "J4") (pin "P2") (pinfunction "2_P2") (pintype "passive"))
      (node (ref "R34") (pin "2") (pinfunction "2_2") (pintype "passive"))
    )
    (net (code "101") (name "Net-(J4-3)") (class "Default")
      (node (ref "J4") (pin "P3") (pinfunction "3_P3") (pintype "passive"))
      (node (ref "R39") (pin "2") (pinfunction "2_2") (pintype "passive"))
    )
    (net (code "102") (name "Net-(J5-2)") (class "Default")
      (node (ref "J5") (pin "P2") (pinfunction "2_P2") (pintype "passive"))
      (node (ref "R44") (pin "2") (pinfunction "2_2") (pintype "passive"))
    )
    (net (code "103") (name "Net-(J5-3)") (class "Default")
      (node (ref "J5") (pin "P3") (pinfunction "3_P3") (pintype "passive"))
      (node (ref "R55") (pin "1") (pinfunction "1_1") (pintype "passive"))
    )
    (net (code "104") (name "Net-(J6-3)") (class "Default")
      (node (ref "J6") (pin "P3") (pinfunction "3_P3") (pintype "passive"))
      (node (ref "R45") (pin "2") (pinfunction "2_2") (pintype "passive"))
    )
    (net (code "105") (name "Net-(J7-2)") (class "Default")
      (node (ref "J7") (pin "P2") (pinfunction "2_P2") (pintype "passive"))
      (node (ref "R63") (pin "2") (pinfunction "2_2") (pintype "passive"))
    )
    (net (code "106") (name "Net-(J7-3)") (class "Default")
      (node (ref "J7") (pin "P3") (pinfunction "3_P3") (pintype "passive"))
      (node (ref "R78") (pin "2") (pinfunction "2_2") (pintype "passive"))
    )
    (net (code "107") (name "Net-(J8-2)") (class "Default")
      (node (ref "J8") (pin "P2") (pinfunction "2_P2") (pintype "passive"))
      (node (ref "R70") (pin "2") (pinfunction "2_2") (pintype "passive"))
    )
    (net (code "108") (name "Net-(J8-3)") (class "Default")
      (node (ref "J8") (pin "P3") (pinfunction "3_P3") (pintype "passive"))
      (node (ref "R84") (pin "1") (pinfunction "1_1") (pintype "passive"))
    )
    (net (code "109") (name "Net-(J9-3)") (class "Default")
      (node (ref "J9") (pin "P3") (pinfunction "3_P3") (pintype "passive"))
      (node (ref "R71") (pin "2") (pinfunction "2_2") (pintype "passive"))
    )
    (net (code "110") (name "Net-(J10-2)") (class "Default")
      (node (ref "J10") (pin "P2") (pinfunction "2_P2") (pintype "passive"))
      (node (ref "R95") (pin "2") (pinfunction "2_2") (pintype "passive"))
    )
    (net (code "111") (name "Net-(J10-3)") (class "Default")
      (node (ref "J10") (pin "P3") (pinfunction "3_P3") (pintype "passive"))
      (node (ref "R102") (pin "2") (pinfunction "2_2") (pintype "passive"))
    )
    (net (code "112") (name "Net-(J11-3)") (class "Default")
      (node (ref "J11") (pin "P3") (pinfunction "3_P3") (pintype "passive"))
      (node (ref "R116") (pin "1") (pinfunction "1_1") (pintype "passive"))
    )
    (net (code "113") (name "Net-(J12-3)") (class "Default")
      (node (ref "J12") (pin "P3") (pinfunction "3_P3") (pintype "passive"))
      (node (ref "R106") (pin "2") (pinfunction "2_2") (pintype "passive"))
    )
    (net (code "114") (name "Net-(JP5-Pad10)") (class "Default")
      (node (ref "JP5") (pin "10") (pinfunction "10_10") (pintype "passive"))
      (node (ref "JP5") (pin "9") (pinfunction "9_9") (pintype "passive"))
      (node (ref "P1") (pin "2") (pinfunction "2_2") (pintype "bidirectional"))
    )
    (net (code "115") (name "Net-(L2-Pad2)") (class "Default")
      (node (ref "L2") (pin "2") (pinfunction "2_2") (pintype "passive"))
      (node (ref "P1") (pin "1") (pinfunction "1_1") (pintype "bidirectional"))
    )
    (net (code "116") (name "Net-(R4-S)") (class "Default")
      (node (ref "R16") (pin "1") (pinfunction "1_1") (pintype "passive"))
      (node (ref "R4") (pin "P$2") (pinfunction "S_P$2") (pintype "passive"))
    )
    (net (code "117") (name "Net-(R5-S)") (class "Default")
      (node (ref "R11") (pin "1") (pinfunction "1_1") (pintype "passive"))
      (node (ref "R5") (pin "P$2") (pinfunction "S_P$2") (pintype "passive"))
    )
    (net (code "118") (name "Net-(R36-S)") (class "Default")
      (node (ref "R36") (pin "P$2") (pinfunction "S_P$2") (pintype "passive"))
      (node (ref "R49") (pin "1") (pinfunction "1_1") (pintype "passive"))
    )
    (net (code "119") (name "Net-(R37-S)") (class "Default")
      (node (ref "R37") (pin "P$2") (pinfunction "S_P$2") (pintype "passive"))
      (node (ref "R45") (pin "1") (pinfunction "1_1") (pintype "passive"))
    )
    (net (code "120") (name "Net-(R64-S)") (class "Default")
      (node (ref "R64") (pin "P$2") (pinfunction "S_P$2") (pintype "passive"))
      (node (ref "R76") (pin "1") (pinfunction "1_1") (pintype "passive"))
    )
    (net (code "121") (name "Net-(R65-S)") (class "Default")
      (node (ref "R65") (pin "P$2") (pinfunction "S_P$2") (pintype "passive"))
      (node (ref "R71") (pin "1") (pinfunction "1_1") (pintype "passive"))
    )
    (net (code "122") (name "Net-(R97-S)") (class "Default")
      (node (ref "R109") (pin "1") (pinfunction "1_1") (pintype "passive"))
      (node (ref "R97") (pin "P$2") (pinfunction "S_P$2") (pintype "passive"))
    )
    (net (code "123") (name "Net-(R98-S)") (class "Default")
      (node (ref "R106") (pin "1") (pinfunction "1_1") (pintype "passive"))
      (node (ref "R98") (pin "P$2") (pinfunction "S_P$2") (pintype "passive"))
    )
    (net (code "124") (name "VCC") (class "Default")
      (node (ref "C11") (pin "1") (pinfunction "1_1") (pintype "passive"))
      (node (ref "C18") (pin "1") (pinfunction "1_1") (pintype "passive"))
      (node (ref "C2") (pin "+") (pinfunction "+_+") (pintype "passive"))
      (node (ref "C21") (pin "1") (pinfunction "1_1") (pintype "passive"))
      (node (ref "C24") (pin "1") (pinfunction "1_1") (pintype "passive"))
      (node (ref "C30") (pin "1") (pinfunction "1_1") (pintype "passive"))
      (node (ref "C32") (pin "1") (pinfunction "1_1") (pintype "passive"))
      (node (ref "C36") (pin "1") (pinfunction "1_1") (pintype "passive"))
      (node (ref "C43") (pin "1") (pinfunction "1_1") (pintype "passive"))
      (node (ref "C46") (pin "1") (pinfunction "1_1") (pintype "passive"))
      (node (ref "C5") (pin "1") (pinfunction "1_1") (pintype "passive"))
      (node (ref "C7") (pin "1") (pinfunction "1_1") (pintype "passive"))
      (node (ref "IC1") (pin "4") (pinfunction "V+_4") (pintype "power_in"))
      (node (ref "IC10") (pin "16") (pinfunction "V+_16") (pintype "power_in"))
      (node (ref "IC11") (pin "4") (pinfunction "V+_4") (pintype "power_in"))
      (node (ref "IC12") (pin "4") (pinfunction "V+_4") (pintype "power_in"))
      (node (ref "IC2") (pin "4") (pinfunction "V+_4") (pintype "power_in"))
      (node (ref "IC3") (pin "16") (pinfunction "V+_16") (pintype "power_in"))
      (node (ref "IC4") (pin "4") (pinfunction "V+_4") (pintype "power_in"))
      (node (ref "IC5") (pin "4") (pinfunction "V+_4") (pintype "power_in"))
      (node (ref "IC8") (pin "4") (pinfunction "V+_4") (pintype "power_in"))
      (node (ref "IC9") (pin "4") (pinfunction "V+_4") (pintype "power_in"))
      (node (ref "L1") (pin "1") (pinfunction "1_1") (pintype "passive"))
      (node (ref "R25") (pin "1") (pinfunction "1_1") (pintype "passive"))
      (node (ref "R59") (pin "1") (pinfunction "1_1") (pintype "passive"))
      (node (ref "R86") (pin "1") (pinfunction "1_1") (pintype "passive"))
    )
    (net (code "125") (name "VEE") (class "Default")
      (node (ref "C1") (pin "-") (pinfunction "-_-") (pintype "passive"))
      (node (ref "C16") (pin "2") (pinfunction "2_2") (pintype "passive"))
      (node (ref "C17") (pin "2") (pinfunction "2_2") (pintype "passive"))
      (node (ref "C22") (pin "2") (pinfunction "2_2") (pintype "passive"))
      (node (ref "C25") (pin "1") (pinfunction "1_1") (pintype "passive"))
      (node (ref "C29") (pin "2") (pinfunction "2_2") (pintype "passive"))
      (node (ref "C33") (pin "2") (pinfunction "2_2") (pintype "passive"))
      (node (ref "C4") (pin "2") (pinfunction "2_2") (pintype "passive"))
      (node (ref "C41") (pin "2") (pinfunction "2_2") (pintype "passive"))
      (node (ref "C42") (pin "2") (pinfunction "2_2") (pintype "passive"))
      (node (ref "C47") (pin "2") (pinfunction "2_2") (pintype "passive"))
      (node (ref "C8") (pin "2") (pinfunction "2_2") (pintype "passive"))
      (node (ref "D1") (pin "A") (pinfunction "A_A") (pintype "passive"))
      (node (ref "IC1") (pin "11") (pinfunction "V-_11") (pintype "power_in"))
      (node (ref "IC10") (pin "9") (pinfunction "V-_9") (pintype "power_in"))
      (node (ref "IC11") (pin "11") (pinfunction "V-_11") (pintype "power_in"))
      (node (ref "IC12") (pin "11") (pinfunction "V-_11") (pintype "power_in"))
      (node (ref "IC2") (pin "11") (pinfunction "V-_11") (pintype "power_in"))
      (node (ref "IC3") (pin "9") (pinfunction "V-_9") (pintype "power_in"))
      (node (ref "IC4") (pin "11") (pinfunction "V-_11") (pintype "power_in"))
      (node (ref "IC5") (pin "11") (pinfunction "V-_11") (pintype "power_in"))
      (node (ref "IC8") (pin "11") (pinfunction "V-_11") (pintype "power_in"))
      (node (ref "IC9") (pin "11") (pinfunction "V-_11") (pintype "power_in"))
      (node (ref "L2") (pin "1") (pinfunction "1_1") (pintype "passive"))
      (node (ref "R60") (pin "1") (pinfunction "1_1") (pintype "passive"))
    )
    (net (code "126") (name "unconnected-(J11-2-PadP2)") (class "Default")
      (node (ref "J11") (pin "P2") (pinfunction "2_P2") (pintype "passive"))
    )
  )
)
